# Audio-DAC.net
KiCad netlist of a schematic drawn in EAGLE
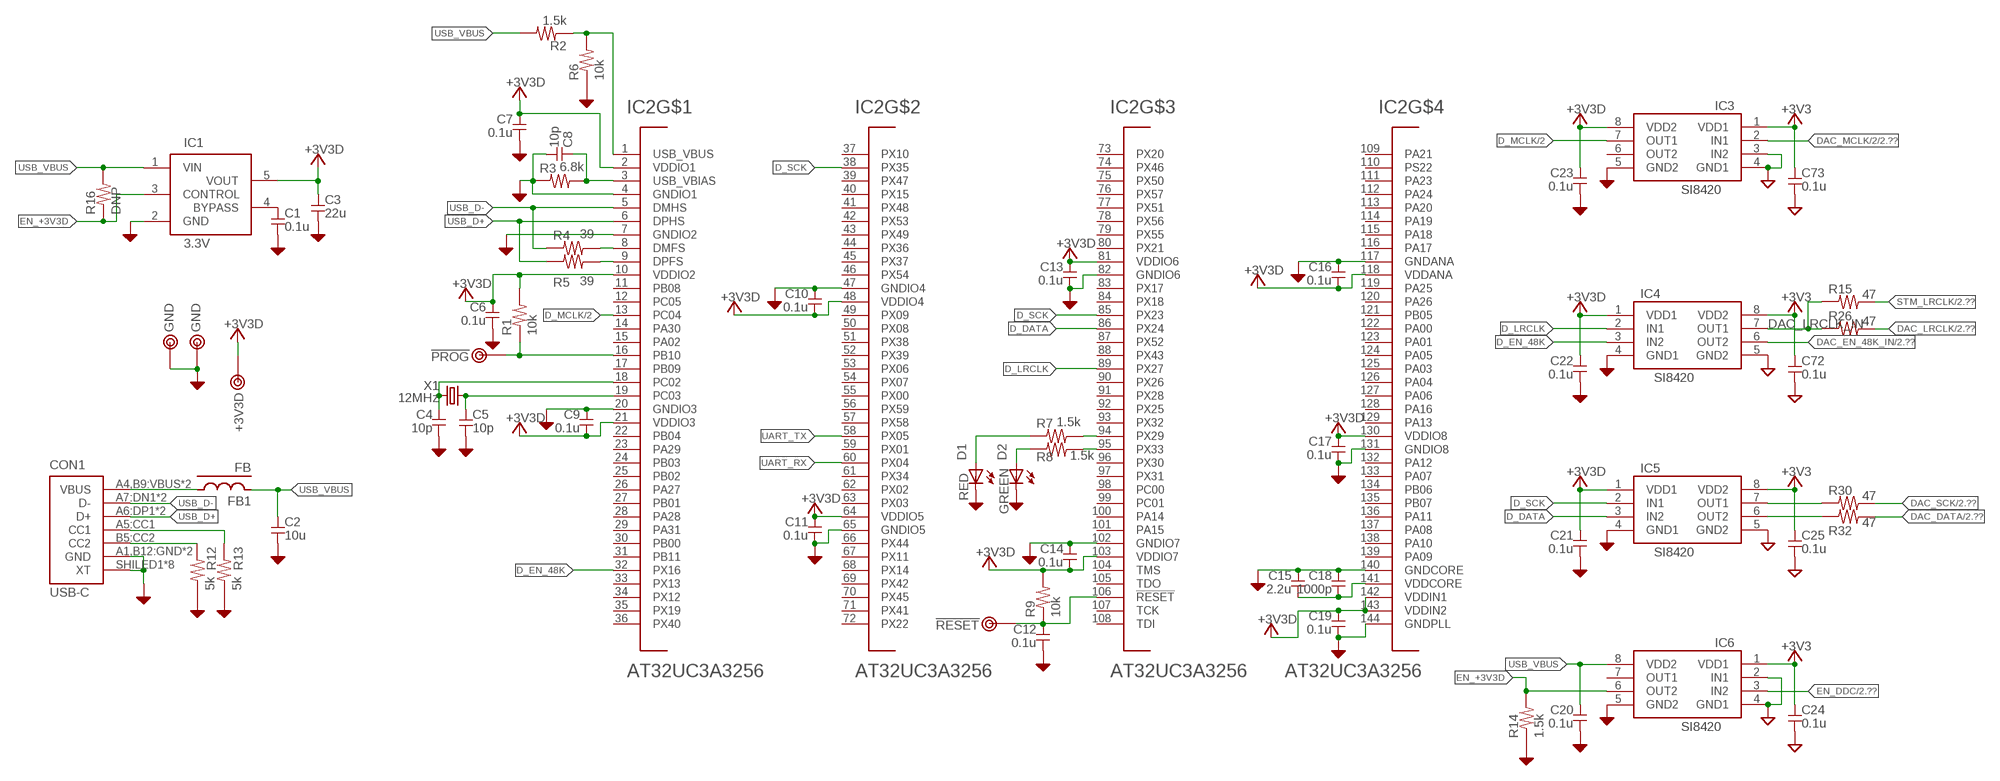
[diagram p0: schematic, sheet 1]
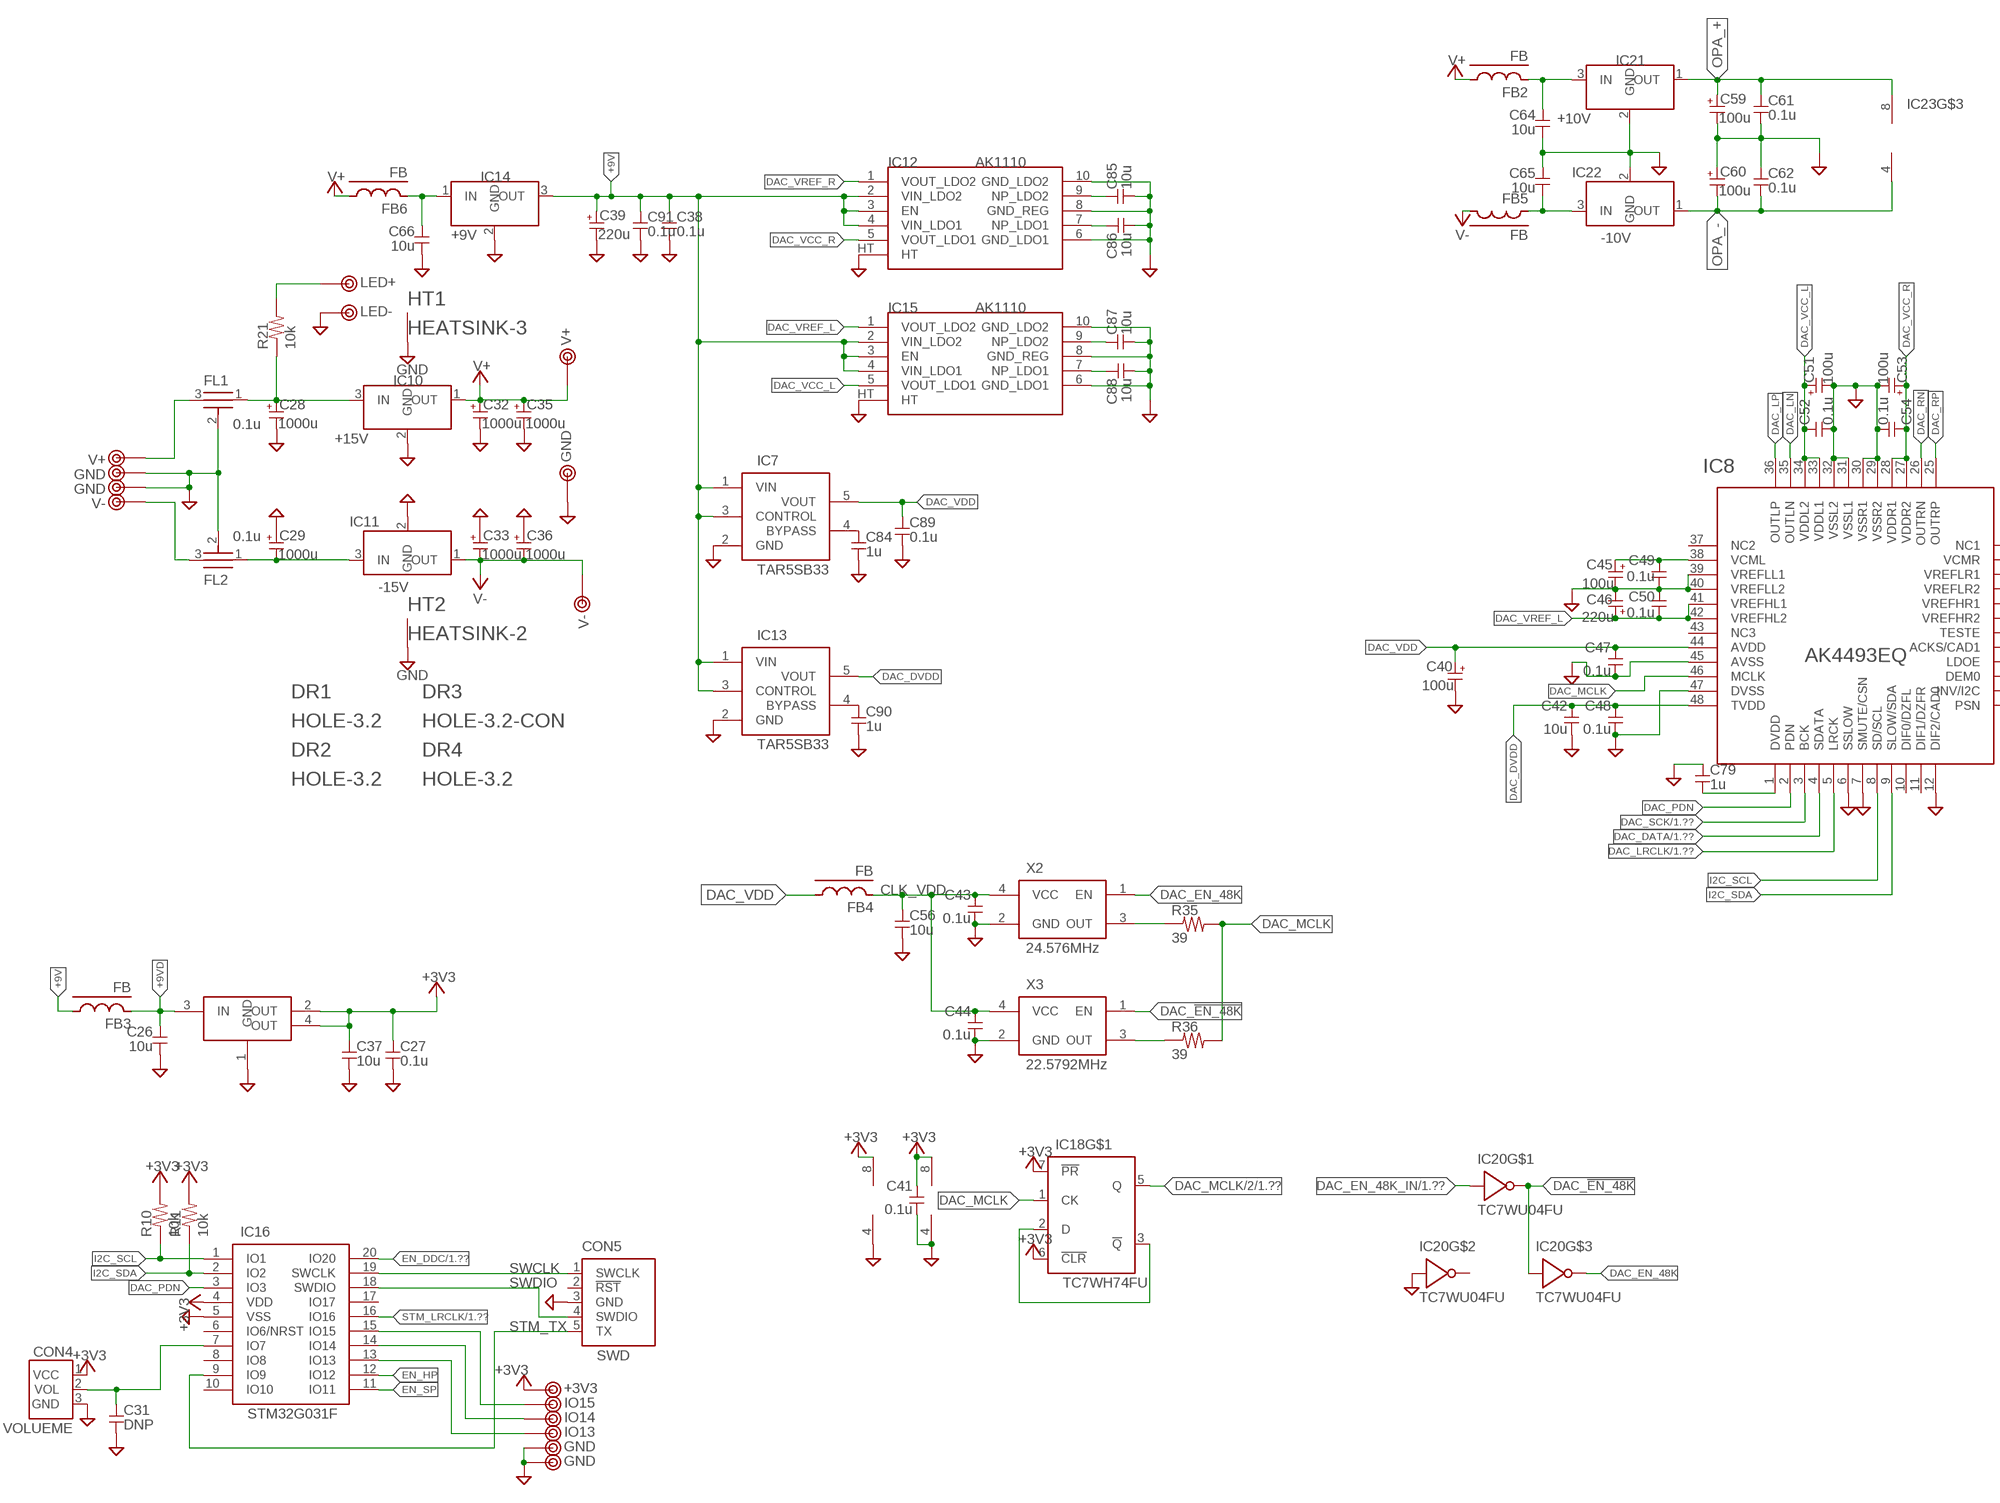
[diagram p1: schematic, sheet 2, part 1 of 2]
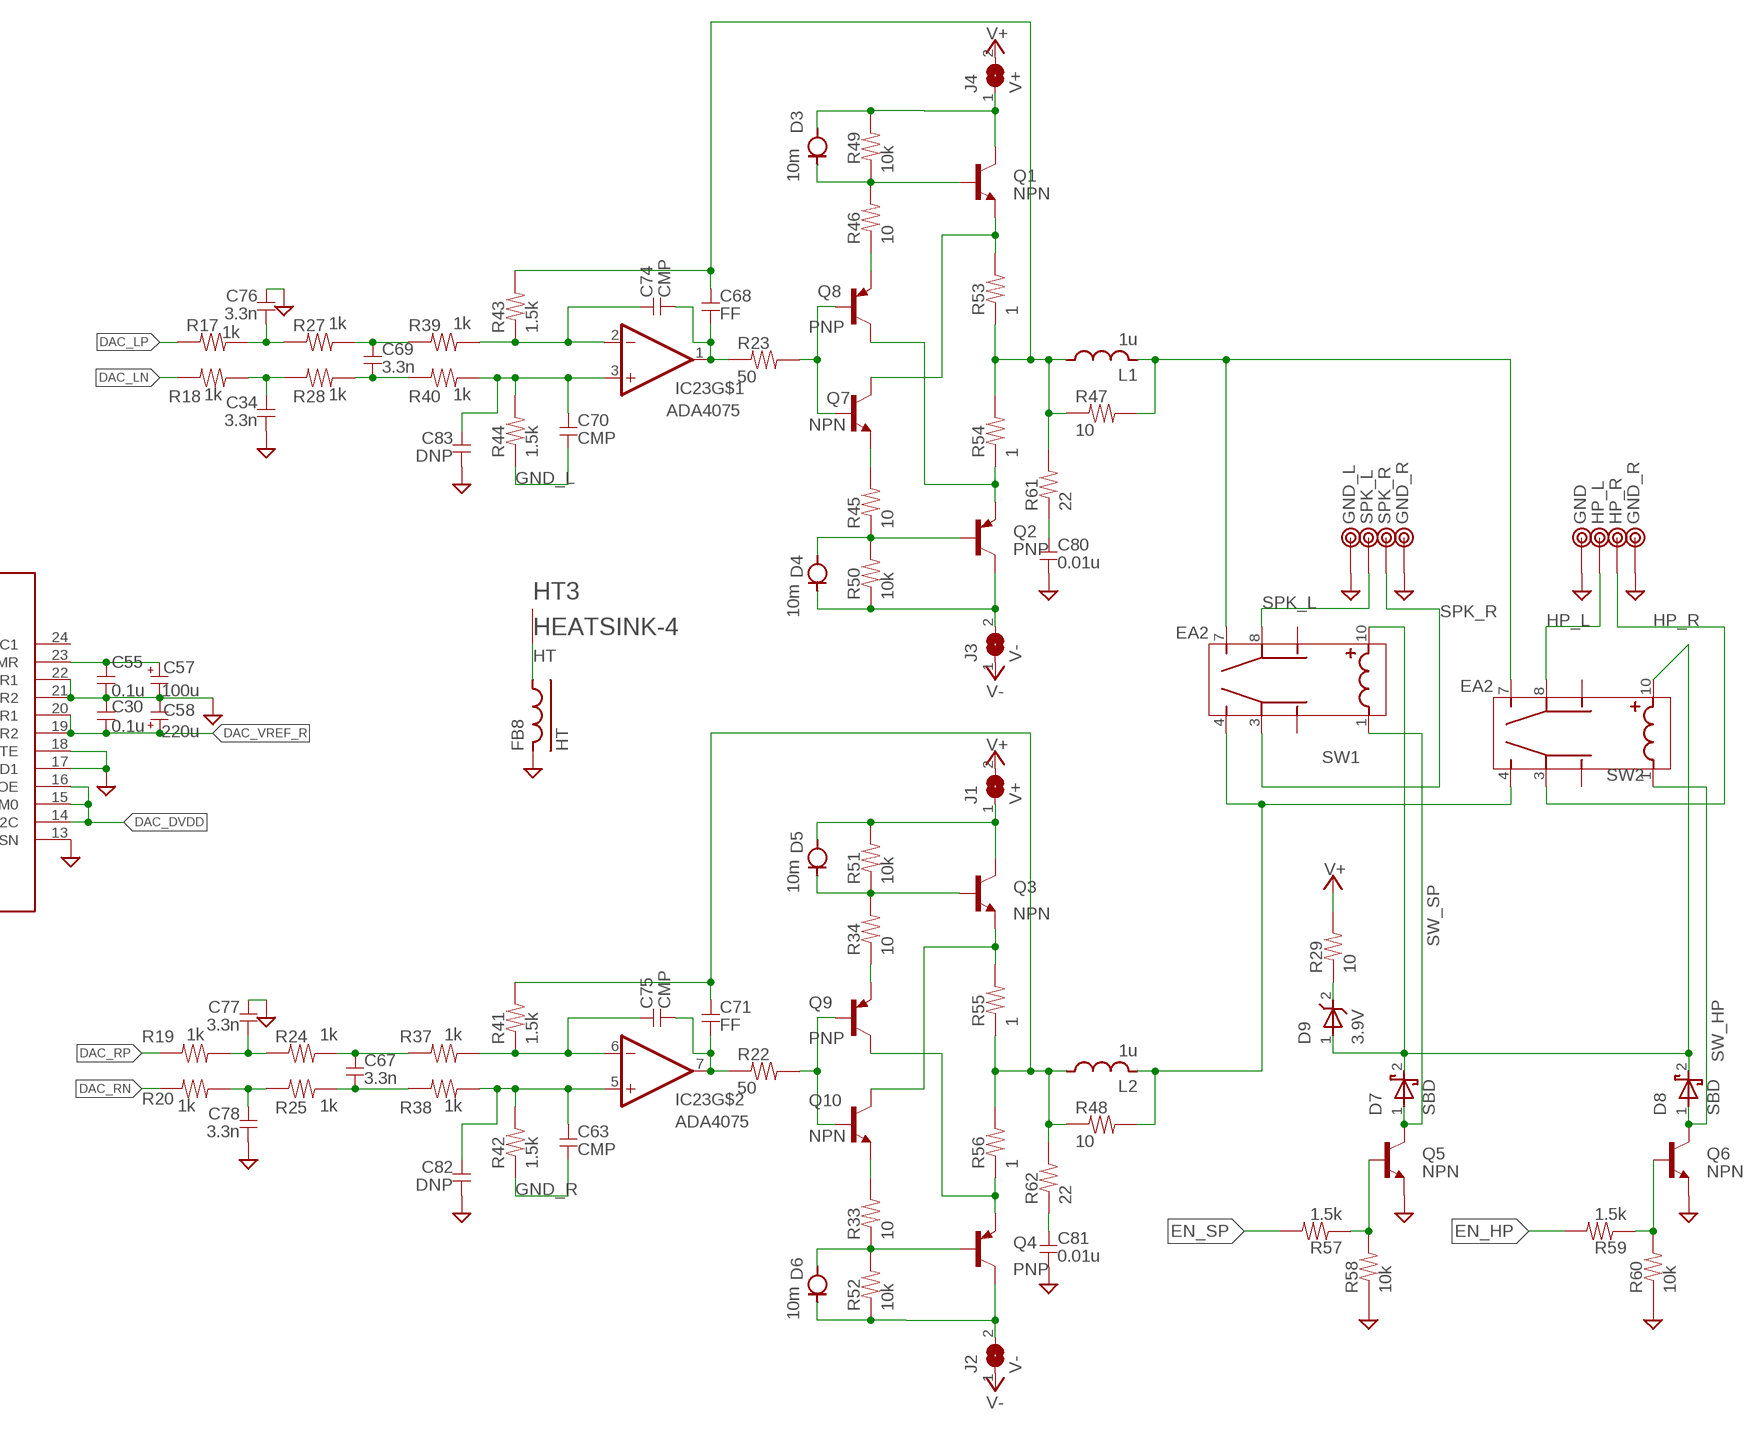
[diagram p2: schematic, sheet 2, part 2 of 2]

(export (version "E")
  (design (tool "Eeschema 10.0.6"))
  (components
    (comp (ref "C26")
      (value "10u")
      (footprint "eagle-import:2012")
      (libsource (lib "eagle-import") (part "C-2012"))
    )
    (comp (ref "C27")
      (value "0.1u")
      (footprint "eagle-import:1608C")
      (libsource (lib "eagle-import") (part "C-1608"))
    )
    (comp (ref "C28")
      (value "1000u")
      (footprint "eagle-import:E5-13")
      (libsource (lib "eagle-import") (part "CPOLE5-13"))
    )
    (comp (ref "C29")
      (value "1000u")
      (footprint "eagle-import:E5-13")
      (libsource (lib "eagle-import") (part "CPOLE5-13"))
    )
    (comp (ref "C30")
      (value "0.1u")
      (footprint "eagle-import:1608C")
      (libsource (lib "eagle-import") (part "C-1608"))
    )
    (comp (ref "C31")
      (value "DNP")
      (footprint "eagle-import:1608C")
      (libsource (lib "eagle-import") (part "C-1608"))
    )
    (comp (ref "C32")
      (value "1000u")
      (footprint "eagle-import:E5-10")
      (libsource (lib "eagle-import") (part "CPOLE5-10"))
    )
    (comp (ref "C33")
      (value "1000u")
      (footprint "eagle-import:E5-10")
      (libsource (lib "eagle-import") (part "CPOLE5-10"))
    )
    (comp (ref "C34")
      (value "3.3n")
      (footprint "eagle-import:1608C")
      (libsource (lib "eagle-import") (part "C-1608"))
    )
    (comp (ref "C35")
      (value "1000u")
      (footprint "eagle-import:E5-10")
      (libsource (lib "eagle-import") (part "CPOLE5-10"))
    )
    (comp (ref "C36")
      (value "1000u")
      (footprint "eagle-import:E5-10")
      (libsource (lib "eagle-import") (part "CPOLE5-10"))
    )
    (comp (ref "C37")
      (value "10u")
      (footprint "eagle-import:2012")
      (libsource (lib "eagle-import") (part "C-2012"))
    )
    (comp (ref "C38")
      (value "0.1u")
      (footprint "eagle-import:1608C")
      (libsource (lib "eagle-import") (part "C-1608"))
    )
    (comp (ref "C39")
      (value "220u")
      (footprint "eagle-import:E2,5-8")
      (libsource (lib "eagle-import") (part "CPOLE2.5-8"))
    )
    (comp (ref "C40")
      (value "100u")
      (footprint "eagle-import:E2.5-6.5")
      (libsource (lib "eagle-import") (part "CPOLE2.5-6.5"))
    )
    (comp (ref "C41")
      (value "0.1u")
      (footprint "eagle-import:1608C")
      (libsource (lib "eagle-import") (part "C-1608"))
    )
    (comp (ref "C42")
      (value "10u")
      (footprint "eagle-import:2012")
      (libsource (lib "eagle-import") (part "C-2012"))
    )
    (comp (ref "C43")
      (value "0.1u")
      (footprint "eagle-import:1608C")
      (libsource (lib "eagle-import") (part "C-1608"))
    )
    (comp (ref "C44")
      (value "0.1u")
      (footprint "eagle-import:1608C")
      (libsource (lib "eagle-import") (part "C-1608"))
    )
    (comp (ref "C45")
      (value "100u")
      (footprint "eagle-import:E2.5-6.5")
      (libsource (lib "eagle-import") (part "CPOLE2.5-6.5"))
    )
    (comp (ref "C46")
      (value "220u")
      (footprint "eagle-import:E2.5-6.5")
      (libsource (lib "eagle-import") (part "CPOLE2.5-6.5"))
    )
    (comp (ref "C47")
      (value "0.1u")
      (footprint "eagle-import:1608C")
      (libsource (lib "eagle-import") (part "C-1608"))
    )
    (comp (ref "C48")
      (value "0.1u")
      (footprint "eagle-import:1608C")
      (libsource (lib "eagle-import") (part "C-1608"))
    )
    (comp (ref "C49")
      (value "0.1u")
      (footprint "eagle-import:1608C")
      (libsource (lib "eagle-import") (part "C-1608"))
    )
    (comp (ref "C50")
      (value "0.1u")
      (footprint "eagle-import:1608C")
      (libsource (lib "eagle-import") (part "C-1608"))
    )
    (comp (ref "C51")
      (value "100u")
      (footprint "eagle-import:E2.5-6.5")
      (libsource (lib "eagle-import") (part "CPOLE2.5-6.5"))
    )
    (comp (ref "C52")
      (value "0.1u")
      (footprint "eagle-import:1608C")
      (libsource (lib "eagle-import") (part "C-1608"))
    )
    (comp (ref "C53")
      (value "100u")
      (footprint "eagle-import:E2.5-6.5")
      (libsource (lib "eagle-import") (part "CPOLE2.5-6.5"))
    )
    (comp (ref "C54")
      (value "0.1u")
      (footprint "eagle-import:1608C")
      (libsource (lib "eagle-import") (part "C-1608"))
    )
    (comp (ref "C55")
      (value "0.1u")
      (footprint "eagle-import:1608C")
      (libsource (lib "eagle-import") (part "C-1608"))
    )
    (comp (ref "C56")
      (value "10u")
      (footprint "eagle-import:2012")
      (libsource (lib "eagle-import") (part "C-2012"))
    )
    (comp (ref "C57")
      (value "100u")
      (footprint "eagle-import:E2.5-6.5")
      (libsource (lib "eagle-import") (part "CPOLE2.5-6.5"))
    )
    (comp (ref "C58")
      (value "220u")
      (footprint "eagle-import:E2.5-6.5")
      (libsource (lib "eagle-import") (part "CPOLE2.5-6.5"))
    )
    (comp (ref "C59")
      (value "100u")
      (footprint "eagle-import:E2,5-8")
      (libsource (lib "eagle-import") (part "CPOLE2.5-8"))
    )
    (comp (ref "C60")
      (value "100u")
      (footprint "eagle-import:E2,5-8")
      (libsource (lib "eagle-import") (part "CPOLE2.5-8"))
    )
    (comp (ref "C61")
      (value "0.1u")
      (footprint "eagle-import:1608C")
      (libsource (lib "eagle-import") (part "C-1608"))
    )
    (comp (ref "C62")
      (value "0.1u")
      (footprint "eagle-import:1608C")
      (libsource (lib "eagle-import") (part "C-1608"))
    )
    (comp (ref "C63")
      (value "CMP")
      (footprint "eagle-import:1608C")
      (libsource (lib "eagle-import") (part "C-1608"))
    )
    (comp (ref "C64")
      (value "10u")
      (footprint "eagle-import:2012")
      (libsource (lib "eagle-import") (part "C-2012"))
    )
    (comp (ref "C65")
      (value "10u")
      (footprint "eagle-import:2012")
      (libsource (lib "eagle-import") (part "C-2012"))
    )
    (comp (ref "C66")
      (value "10u")
      (footprint "eagle-import:2012")
      (libsource (lib "eagle-import") (part "C-2012"))
    )
    (comp (ref "C67")
      (value "3.3n")
      (footprint "eagle-import:1608C")
      (libsource (lib "eagle-import") (part "C-1608"))
    )
    (comp (ref "C68")
      (value "FF")
      (footprint "eagle-import:1608C")
      (libsource (lib "eagle-import") (part "C-1608"))
    )
    (comp (ref "C69")
      (value "3.3n")
      (footprint "eagle-import:1608C")
      (libsource (lib "eagle-import") (part "C-1608"))
    )
    (comp (ref "C70")
      (value "CMP")
      (footprint "eagle-import:1608C")
      (libsource (lib "eagle-import") (part "C-1608"))
    )
    (comp (ref "C71")
      (value "FF")
      (footprint "eagle-import:1608C")
      (libsource (lib "eagle-import") (part "C-1608"))
    )
    (comp (ref "C74")
      (value "CMP")
      (footprint "eagle-import:1608C")
      (libsource (lib "eagle-import") (part "C-1608"))
    )
    (comp (ref "C75")
      (value "CMP")
      (footprint "eagle-import:1608C")
      (libsource (lib "eagle-import") (part "C-1608"))
    )
    (comp (ref "C76")
      (value "3.3n")
      (footprint "eagle-import:1608C")
      (libsource (lib "eagle-import") (part "C-1608"))
    )
    (comp (ref "C77")
      (value "3.3n")
      (footprint "eagle-import:1608C")
      (libsource (lib "eagle-import") (part "C-1608"))
    )
    (comp (ref "C78")
      (value "3.3n")
      (footprint "eagle-import:1608C")
      (libsource (lib "eagle-import") (part "C-1608"))
    )
    (comp (ref "C79")
      (value "1u")
      (footprint "eagle-import:1608C")
      (libsource (lib "eagle-import") (part "C-1608"))
    )
    (comp (ref "C80")
      (value "0.01u")
      (footprint "eagle-import:2012")
      (libsource (lib "eagle-import") (part "C-2012"))
    )
    (comp (ref "C81")
      (value "0.01u")
      (footprint "eagle-import:2012")
      (libsource (lib "eagle-import") (part "C-2012"))
    )
    (comp (ref "C82")
      (value "DNP")
      (footprint "eagle-import:1608C")
      (libsource (lib "eagle-import") (part "C-1608"))
    )
    (comp (ref "C83")
      (value "DNP")
      (footprint "eagle-import:1608C")
      (libsource (lib "eagle-import") (part "C-1608"))
    )
    (comp (ref "C84")
      (value "1u")
      (footprint "eagle-import:1608C")
      (libsource (lib "eagle-import") (part "C-1608"))
    )
    (comp (ref "C85")
      (value "10u")
      (footprint "eagle-import:2012")
      (libsource (lib "eagle-import") (part "C-2012"))
    )
    (comp (ref "C86")
      (value "10u")
      (footprint "eagle-import:2012")
      (libsource (lib "eagle-import") (part "C-2012"))
    )
    (comp (ref "C87")
      (value "10u")
      (footprint "eagle-import:2012")
      (libsource (lib "eagle-import") (part "C-2012"))
    )
    (comp (ref "C88")
      (value "10u")
      (footprint "eagle-import:2012")
      (libsource (lib "eagle-import") (part "C-2012"))
    )
    (comp (ref "C89")
      (value "0.1u")
      (footprint "eagle-import:1608C")
      (libsource (lib "eagle-import") (part "C-1608"))
    )
    (comp (ref "C90")
      (value "1u")
      (footprint "eagle-import:1608C")
      (libsource (lib "eagle-import") (part "C-1608"))
    )
    (comp (ref "C91")
      (value "0.1u")
      (footprint "eagle-import:1608C")
      (libsource (lib "eagle-import") (part "C-1608"))
    )
    (comp (ref "CON4")
      (value "VOLUEME")
      (footprint "eagle-import:VOL_CON")
      (libsource (lib "eagle-import") (part "VOL_CON"))
    )
    (comp (ref "CON5")
      (value "SWD")
      (footprint "eagle-import:SWD_CON")
      (libsource (lib "eagle-import") (part "SWD_CON"))
    )
    (comp (ref "D3")
      (value "10m")
      (footprint "eagle-import:SOD123")
      (libsource (lib "eagle-import") (part "CRD-SMD"))
    )
    (comp (ref "D4")
      (value "10m")
      (footprint "eagle-import:SOD123")
      (libsource (lib "eagle-import") (part "CRD-SMD"))
    )
    (comp (ref "D5")
      (value "10m")
      (footprint "eagle-import:SOD123")
      (libsource (lib "eagle-import") (part "CRD-SMD"))
    )
    (comp (ref "D6")
      (value "10m")
      (footprint "eagle-import:SOD123")
      (libsource (lib "eagle-import") (part "CRD-SMD"))
    )
    (comp (ref "D7")
      (value "SBD")
      (footprint "eagle-import:SOD123")
      (libsource (lib "eagle-import") (part "SBD-1A2"))
    )
    (comp (ref "D8")
      (value "SBD")
      (footprint "eagle-import:SOD123")
      (libsource (lib "eagle-import") (part "SBD-1A2"))
    )
    (comp (ref "D9")
      (value "3.9V")
      (footprint "eagle-import:SOD123")
      (libsource (lib "eagle-import") (part "ZENER-SMD"))
    )
    (comp (ref "DR1")
      (value "HOLE-3.2")
      (footprint "eagle-import:HOLE_3.2")
      (libsource (lib "eagle-import") (part "HOLE-3.2"))
    )
    (comp (ref "DR2")
      (value "HOLE-3.2")
      (footprint "eagle-import:HOLE_3.2")
      (libsource (lib "eagle-import") (part "HOLE-3.2"))
    )
    (comp (ref "DR3")
      (value "HOLE-3.2-CON")
      (footprint "eagle-import:HOLE_3.2_CON")
      (libsource (lib "eagle-import") (part "HOLE-3.2-CON"))
    )
    (comp (ref "DR4")
      (value "HOLE-3.2")
      (footprint "eagle-import:HOLE_3.2")
      (libsource (lib "eagle-import") (part "HOLE-3.2"))
    )
    (comp (ref "FB2")
      (value "FB")
      (footprint "eagle-import:1608-J")
      (libsource (lib "eagle-import") (part "FB"))
    )
    (comp (ref "FB3")
      (value "FB")
      (footprint "eagle-import:1608-J")
      (libsource (lib "eagle-import") (part "FB"))
    )
    (comp (ref "FB4")
      (value "FB")
      (footprint "eagle-import:1608-J")
      (libsource (lib "eagle-import") (part "FB"))
    )
    (comp (ref "FB5")
      (value "FB")
      (footprint "eagle-import:1608-J")
      (libsource (lib "eagle-import") (part "FB"))
    )
    (comp (ref "FB6")
      (value "FB")
      (footprint "eagle-import:1608-J")
      (libsource (lib "eagle-import") (part "FB"))
    )
    (comp (ref "FB8")
      (value "HT")
      (footprint "eagle-import:2012-J")
      (libsource (lib "eagle-import") (part "FB-2012"))
    )
    (comp (ref "FL1")
      (value "0.1u")
      (footprint "eagle-import:FL1")
      (libsource (lib "eagle-import") (part "FL"))
    )
    (comp (ref "FL2")
      (value "0.1u")
      (footprint "eagle-import:FL1")
      (libsource (lib "eagle-import") (part "FL"))
    )
    (comp (ref "HT1")
      (value "HEATSINK-3")
      (footprint "eagle-import:HEATSINK3")
      (libsource (lib "eagle-import") (part "HEATSINK-3"))
    )
    (comp (ref "HT2")
      (value "HEATSINK-2")
      (footprint "eagle-import:HEATSINK2")
      (libsource (lib "eagle-import") (part "HEATSINK-2"))
    )
    (comp (ref "HT3")
      (value "HEATSINK-4")
      (footprint "eagle-import:HEATSINK4")
      (libsource (lib "eagle-import") (part "HEATSINK-4"))
    )
    (comp (ref "IC7")
      (value "TAR5SB33")
      (footprint "eagle-import:SOT23-5")
      (libsource (lib "eagle-import") (part "TAR5SB33"))
    )
    (comp (ref "IC8")
      (value "AK4493EQ")
      (footprint "eagle-import:LQFP48")
      (libsource (lib "eagle-import") (part "AK4493EQ"))
    )
    (comp (ref "IC9")
      (value "AZ1086H-3.3")
      (footprint "eagle-import:SOT223")
      (libsource (lib "eagle-import") (part "AZ1086?-H3.3"))
    )
    (comp (ref "IC10")
      (value "+15V")
      (footprint "eagle-import:REGULATOR_LED")
      (libsource (lib "eagle-import") (part "78X-LED"))
    )
    (comp (ref "IC11")
      (value "-15V")
      (footprint "eagle-import:REGULATOR_LED")
      (libsource (lib "eagle-import") (part "79X-LED"))
    )
    (comp (ref "IC12")
      (value "AK1110")
      (footprint "eagle-import:PLP10-SMD")
      (libsource (lib "eagle-import") (part "AK1110-SMD"))
    )
    (comp (ref "IC13")
      (value "TAR5SB33")
      (footprint "eagle-import:SOT23-5")
      (libsource (lib "eagle-import") (part "TAR5SB33"))
    )
    (comp (ref "IC14")
      (value "+9V")
      (footprint "eagle-import:TO-220")
      (libsource (lib "eagle-import") (part "78X-1"))
    )
    (comp (ref "IC15")
      (value "AK1110")
      (footprint "eagle-import:PLP10-SMD")
      (libsource (lib "eagle-import") (part "AK1110-SMD"))
    )
    (comp (ref "IC16")
      (value "STM32G031F")
      (footprint "eagle-import:TSSOP20")
      (libsource (lib "eagle-import") (part "STM32G031F"))
    )
    (comp (ref "IC18")
      (value "TC7WH74FU")
      (footprint "eagle-import:SSOP8-P-0.65")
      (libsource (lib "eagle-import") (part "TC7WH74FU"))
    )
    (comp (ref "IC20")
      (value "TC7WU04FU")
      (footprint "eagle-import:SSOP8-P-0.65")
      (libsource (lib "eagle-import") (part "TC7WU04FU"))
    )
    (comp (ref "IC21")
      (value "+10V")
      (footprint "eagle-import:REGULATOR_LED")
      (libsource (lib "eagle-import") (part "78X-LED"))
    )
    (comp (ref "IC22")
      (value "-10V")
      (footprint "eagle-import:REGULATOR_LED")
      (libsource (lib "eagle-import") (part "79X-LED"))
    )
    (comp (ref "IC23")
      (value "ADA4075")
      (footprint "eagle-import:SOP8")
      (libsource (lib "eagle-import") (part "OPA-2-SOP"))
    )
    (comp (ref "J1")
      (value "V+")
      (footprint "eagle-import:2012-J")
      (libsource (lib "eagle-import") (part "SJ-2012"))
    )
    (comp (ref "J2")
      (value "V-")
      (footprint "eagle-import:2012-J")
      (libsource (lib "eagle-import") (part "SJ-2012"))
    )
    (comp (ref "J3")
      (value "V-")
      (footprint "eagle-import:2012-J")
      (libsource (lib "eagle-import") (part "SJ-2012"))
    )
    (comp (ref "J4")
      (value "V+")
      (footprint "eagle-import:2012-J")
      (libsource (lib "eagle-import") (part "SJ-2012"))
    )
    (comp (ref "L1")
      (value "1u")
      (footprint "eagle-import:L7-10-2")
      (libsource (lib "eagle-import") (part "L-7-2"))
    )
    (comp (ref "L2")
      (value "1u")
      (footprint "eagle-import:L7-10-2")
      (libsource (lib "eagle-import") (part "L-7-2"))
    )
    (comp (ref "Q1")
      (value "NPN")
      (footprint "eagle-import:TO126")
      (libsource (lib "eagle-import") (part "NPN2SC3422"))
    )
    (comp (ref "Q2")
      (value "PNP")
      (footprint "eagle-import:TO126")
      (libsource (lib "eagle-import") (part "PNP2SA1359"))
    )
    (comp (ref "Q3")
      (value "NPN")
      (footprint "eagle-import:TO126")
      (libsource (lib "eagle-import") (part "NPN2SC3422"))
    )
    (comp (ref "Q4")
      (value "PNP")
      (footprint "eagle-import:TO126")
      (libsource (lib "eagle-import") (part "PNP2SA1359"))
    )
    (comp (ref "Q5")
      (value "NPN")
      (footprint "eagle-import:SC59")
      (libsource (lib "eagle-import") (part "NPN2SC3325"))
    )
    (comp (ref "Q6")
      (value "NPN")
      (footprint "eagle-import:SC59")
      (libsource (lib "eagle-import") (part "NPN2SC3325"))
    )
    (comp (ref "Q7")
      (value "NPN")
      (footprint "eagle-import:SC59")
      (libsource (lib "eagle-import") (part "NPN2SC3325"))
    )
    (comp (ref "Q8")
      (value "PNP")
      (footprint "eagle-import:SC59")
      (libsource (lib "eagle-import") (part "PNP2SA1313"))
    )
    (comp (ref "Q9")
      (value "PNP")
      (footprint "eagle-import:SC59")
      (libsource (lib "eagle-import") (part "PNP2SA1313"))
    )
    (comp (ref "Q10")
      (value "NPN")
      (footprint "eagle-import:SC59")
      (libsource (lib "eagle-import") (part "NPN2SC3325"))
    )
    (comp (ref "R10")
      (value "10k")
      (footprint "eagle-import:1608")
      (libsource (lib "eagle-import") (part "R-1608"))
    )
    (comp (ref "R11")
      (value "10k")
      (footprint "eagle-import:1608")
      (libsource (lib "eagle-import") (part "R-1608"))
    )
    (comp (ref "R17")
      (value "1k")
      (footprint "eagle-import:1608")
      (libsource (lib "eagle-import") (part "R-1608"))
    )
    (comp (ref "R18")
      (value "1k")
      (footprint "eagle-import:1608")
      (libsource (lib "eagle-import") (part "R-1608"))
    )
    (comp (ref "R19")
      (value "1k")
      (footprint "eagle-import:1608")
      (libsource (lib "eagle-import") (part "R-1608"))
    )
    (comp (ref "R20")
      (value "1k")
      (footprint "eagle-import:1608")
      (libsource (lib "eagle-import") (part "R-1608"))
    )
    (comp (ref "R21")
      (value "10k")
      (footprint "eagle-import:2012")
      (libsource (lib "eagle-import") (part "R-2012"))
    )
    (comp (ref "R22")
      (value "50")
      (footprint "eagle-import:1608")
      (libsource (lib "eagle-import") (part "R-1608"))
    )
    (comp (ref "R23")
      (value "50")
      (footprint "eagle-import:1608")
      (libsource (lib "eagle-import") (part "R-1608"))
    )
    (comp (ref "R24")
      (value "1k")
      (footprint "eagle-import:1608")
      (libsource (lib "eagle-import") (part "R-1608"))
    )
    (comp (ref "R25")
      (value "1k")
      (footprint "eagle-import:1608")
      (libsource (lib "eagle-import") (part "R-1608"))
    )
    (comp (ref "R27")
      (value "1k")
      (footprint "eagle-import:1608")
      (libsource (lib "eagle-import") (part "R-1608"))
    )
    (comp (ref "R28")
      (value "1k")
      (footprint "eagle-import:1608")
      (libsource (lib "eagle-import") (part "R-1608"))
    )
    (comp (ref "R29")
      (value "10")
      (footprint "eagle-import:2012")
      (libsource (lib "eagle-import") (part "R-2012"))
    )
    (comp (ref "R33")
      (value "10")
      (footprint "eagle-import:1608")
      (libsource (lib "eagle-import") (part "R-1608"))
    )
    (comp (ref "R34")
      (value "10")
      (footprint "eagle-import:1608")
      (libsource (lib "eagle-import") (part "R-1608"))
    )
    (comp (ref "R35")
      (value "39")
      (footprint "eagle-import:1608-J")
      (libsource (lib "eagle-import") (part "R-1608J"))
    )
    (comp (ref "R36")
      (value "39")
      (footprint "eagle-import:1608-J")
      (libsource (lib "eagle-import") (part "R-1608J"))
    )
    (comp (ref "R37")
      (value "1k")
      (footprint "eagle-import:1608")
      (libsource (lib "eagle-import") (part "R-1608"))
    )
    (comp (ref "R38")
      (value "1k")
      (footprint "eagle-import:1608")
      (libsource (lib "eagle-import") (part "R-1608"))
    )
    (comp (ref "R39")
      (value "1k")
      (footprint "eagle-import:1608")
      (libsource (lib "eagle-import") (part "R-1608"))
    )
    (comp (ref "R40")
      (value "1k")
      (footprint "eagle-import:1608")
      (libsource (lib "eagle-import") (part "R-1608"))
    )
    (comp (ref "R41")
      (value "1.5k")
      (footprint "eagle-import:1608")
      (libsource (lib "eagle-import") (part "R-1608"))
    )
    (comp (ref "R42")
      (value "1.5k")
      (footprint "eagle-import:1608")
      (libsource (lib "eagle-import") (part "R-1608"))
    )
    (comp (ref "R43")
      (value "1.5k")
      (footprint "eagle-import:1608")
      (libsource (lib "eagle-import") (part "R-1608"))
    )
    (comp (ref "R44")
      (value "1.5k")
      (footprint "eagle-import:1608")
      (libsource (lib "eagle-import") (part "R-1608"))
    )
    (comp (ref "R45")
      (value "10")
      (footprint "eagle-import:1608")
      (libsource (lib "eagle-import") (part "R-1608"))
    )
    (comp (ref "R46")
      (value "10")
      (footprint "eagle-import:1608")
      (libsource (lib "eagle-import") (part "R-1608"))
    )
    (comp (ref "R47")
      (value "10")
      (footprint "eagle-import:2012")
      (libsource (lib "eagle-import") (part "R-2012"))
    )
    (comp (ref "R48")
      (value "10")
      (footprint "eagle-import:2012")
      (libsource (lib "eagle-import") (part "R-2012"))
    )
    (comp (ref "R49")
      (value "10k")
      (footprint "eagle-import:1608")
      (libsource (lib "eagle-import") (part "R-1608"))
    )
    (comp (ref "R50")
      (value "10k")
      (footprint "eagle-import:1608")
      (libsource (lib "eagle-import") (part "R-1608"))
    )
    (comp (ref "R51")
      (value "10k")
      (footprint "eagle-import:1608")
      (libsource (lib "eagle-import") (part "R-1608"))
    )
    (comp (ref "R52")
      (value "10k")
      (footprint "eagle-import:1608")
      (libsource (lib "eagle-import") (part "R-1608"))
    )
    (comp (ref "R53")
      (value "1")
      (footprint "eagle-import:0207_2V")
      (libsource (lib "eagle-import") (part "R-2.5"))
    )
    (comp (ref "R54")
      (value "1")
      (footprint "eagle-import:0204_5")
      (libsource (lib "eagle-import") (part "R-5"))
    )
    (comp (ref "R55")
      (value "1")
      (footprint "eagle-import:0207_2V")
      (libsource (lib "eagle-import") (part "R-2.5"))
    )
    (comp (ref "R56")
      (value "1")
      (footprint "eagle-import:0207_2V")
      (libsource (lib "eagle-import") (part "R-2.5"))
    )
    (comp (ref "R57")
      (value "1.5k")
      (footprint "eagle-import:1608")
      (libsource (lib "eagle-import") (part "R-1608"))
    )
    (comp (ref "R58")
      (value "10k")
      (footprint "eagle-import:1608")
      (libsource (lib "eagle-import") (part "R-1608"))
    )
    (comp (ref "R59")
      (value "1.5k")
      (footprint "eagle-import:1608")
      (libsource (lib "eagle-import") (part "R-1608"))
    )
    (comp (ref "R60")
      (value "10k")
      (footprint "eagle-import:1608")
      (libsource (lib "eagle-import") (part "R-1608"))
    )
    (comp (ref "R61")
      (value "22")
      (footprint "eagle-import:2012")
      (libsource (lib "eagle-import") (part "R-2012"))
    )
    (comp (ref "R62")
      (value "22")
      (footprint "eagle-import:2012")
      (libsource (lib "eagle-import") (part "R-2012"))
    )
    (comp (ref "SW1")
      (value "EA2")
      (footprint "eagle-import:EA2")
      (libsource (lib "eagle-import") (part "EA2"))
    )
    (comp (ref "SW2")
      (value "EA2")
      (footprint "eagle-import:EA2")
      (libsource (lib "eagle-import") (part "EA2"))
    )
    (comp (ref "TP5")
      (value "V+")
      (footprint "eagle-import:TESTPIN-BIG")
      (libsource (lib "eagle-import") (part "TESTPIN-BIG"))
    )
    (comp (ref "TP6")
      (value "GND")
      (footprint "eagle-import:TESTPIN-BIG")
      (libsource (lib "eagle-import") (part "TESTPIN-BIG"))
    )
    (comp (ref "TP7")
      (value "GND")
      (footprint "eagle-import:TESTPIN-BIG")
      (libsource (lib "eagle-import") (part "TESTPIN-BIG"))
    )
    (comp (ref "TP8")
      (value "V-")
      (footprint "eagle-import:TESTPIN-BIG")
      (libsource (lib "eagle-import") (part "TESTPIN-BIG"))
    )
    (comp (ref "TP9")
      (value "IO15")
      (footprint "eagle-import:TESTPIN")
      (libsource (lib "eagle-import") (part "TESTPIN"))
    )
    (comp (ref "TP10")
      (value "IO14")
      (footprint "eagle-import:TESTPIN")
      (libsource (lib "eagle-import") (part "TESTPIN"))
    )
    (comp (ref "TP11")
      (value "V+")
      (footprint "eagle-import:TESTPIN-BIG")
      (libsource (lib "eagle-import") (part "TESTPIN-BIG"))
    )
    (comp (ref "TP12")
      (value "IO13")
      (footprint "eagle-import:TESTPIN")
      (libsource (lib "eagle-import") (part "TESTPIN"))
    )
    (comp (ref "TP13")
      (value "GND")
      (footprint "eagle-import:TESTPIN")
      (libsource (lib "eagle-import") (part "TESTPIN"))
    )
    (comp (ref "TP14")
      (value "GND")
      (footprint "eagle-import:TESTPIN")
      (libsource (lib "eagle-import") (part "TESTPIN"))
    )
    (comp (ref "TP15")
      (value "LED+")
      (footprint "eagle-import:TESTPIN")
      (libsource (lib "eagle-import") (part "TESTPIN"))
    )
    (comp (ref "TP16")
      (value "LED-")
      (footprint "eagle-import:TESTPIN")
      (libsource (lib "eagle-import") (part "TESTPIN"))
    )
    (comp (ref "TP17")
      (value "+3V3")
      (footprint "eagle-import:TESTPIN")
      (libsource (lib "eagle-import") (part "TESTPIN"))
    )
    (comp (ref "TP21")
      (value "V-")
      (footprint "eagle-import:TESTPIN-BIG")
      (libsource (lib "eagle-import") (part "TESTPIN-BIG"))
    )
    (comp (ref "TP22")
      (value "GND")
      (footprint "eagle-import:TESTPIN-BIG")
      (libsource (lib "eagle-import") (part "TESTPIN-BIG"))
    )
    (comp (ref "TP27")
      (value "GND_L")
      (footprint "eagle-import:TESTPIN-BIG")
      (libsource (lib "eagle-import") (part "TESTPIN-BIG"))
    )
    (comp (ref "TP28")
      (value "SPK_L")
      (footprint "eagle-import:TESTPIN-BIG")
      (libsource (lib "eagle-import") (part "TESTPIN-BIG"))
    )
    (comp (ref "TP29")
      (value "SPK_R")
      (footprint "eagle-import:TESTPIN-BIG")
      (libsource (lib "eagle-import") (part "TESTPIN-BIG"))
    )
    (comp (ref "TP30")
      (value "GND_R")
      (footprint "eagle-import:TESTPIN-BIG")
      (libsource (lib "eagle-import") (part "TESTPIN-BIG"))
    )
    (comp (ref "TP31")
      (value "GND")
      (footprint "eagle-import:TESTPIN-BIG")
      (libsource (lib "eagle-import") (part "TESTPIN-BIG"))
    )
    (comp (ref "TP32")
      (value "HP_L")
      (footprint "eagle-import:TESTPIN-BIG")
      (libsource (lib "eagle-import") (part "TESTPIN-BIG"))
    )
    (comp (ref "TP33")
      (value "HP_R")
      (footprint "eagle-import:TESTPIN-BIG")
      (libsource (lib "eagle-import") (part "TESTPIN-BIG"))
    )
    (comp (ref "TP34")
      (value "GND_R")
      (footprint "eagle-import:TESTPIN-BIG")
      (libsource (lib "eagle-import") (part "TESTPIN-BIG"))
    )
    (comp (ref "X2")
      (value "24.576MHz")
      (footprint "eagle-import:KC3225")
      (libsource (lib "eagle-import") (part "OSC-KC3225"))
    )
    (comp (ref "X3")
      (value "22.5792MHz")
      (footprint "eagle-import:KC3225")
      (libsource (lib "eagle-import") (part "OSC-KC3225"))
    )
    (comp (ref "C1")
      (value "0.1u")
      (footprint "eagle-import:1608C")
      (libsource (lib "eagle-import") (part "C-1608"))
    )
    (comp (ref "C2")
      (value "10u")
      (footprint "eagle-import:2012")
      (libsource (lib "eagle-import") (part "C-2012"))
    )
    (comp (ref "C3")
      (value "22u")
      (footprint "eagle-import:2012")
      (libsource (lib "eagle-import") (part "C-2012"))
    )
    (comp (ref "C4")
      (value "10p")
      (footprint "eagle-import:1608C")
      (libsource (lib "eagle-import") (part "C-1608"))
    )
    (comp (ref "C5")
      (value "10p")
      (footprint "eagle-import:1608C")
      (libsource (lib "eagle-import") (part "C-1608"))
    )
    (comp (ref "C6")
      (value "0.1u")
      (footprint "eagle-import:1608C")
      (libsource (lib "eagle-import") (part "C-1608"))
    )
    (comp (ref "C7")
      (value "0.1u")
      (footprint "eagle-import:1608C")
      (libsource (lib "eagle-import") (part "C-1608"))
    )
    (comp (ref "C8")
      (value "10p")
      (footprint "eagle-import:1608C")
      (libsource (lib "eagle-import") (part "C-1608"))
    )
    (comp (ref "C9")
      (value "0.1u")
      (footprint "eagle-import:1608C")
      (libsource (lib "eagle-import") (part "C-1608"))
    )
    (comp (ref "C10")
      (value "0.1u")
      (footprint "eagle-import:1608C")
      (libsource (lib "eagle-import") (part "C-1608"))
    )
    (comp (ref "C11")
      (value "0.1u")
      (footprint "eagle-import:1608C")
      (libsource (lib "eagle-import") (part "C-1608"))
    )
    (comp (ref "C12")
      (value "0.1u")
      (footprint "eagle-import:1608C")
      (libsource (lib "eagle-import") (part "C-1608"))
    )
    (comp (ref "C13")
      (value "0.1u")
      (footprint "eagle-import:1608C")
      (libsource (lib "eagle-import") (part "C-1608"))
    )
    (comp (ref "C14")
      (value "0.1u")
      (footprint "eagle-import:1608C")
      (libsource (lib "eagle-import") (part "C-1608"))
    )
    (comp (ref "C15")
      (value "2.2u")
      (footprint "eagle-import:2012")
      (libsource (lib "eagle-import") (part "C-2012"))
    )
    (comp (ref "C16")
      (value "0.1u")
      (footprint "eagle-import:1608C")
      (libsource (lib "eagle-import") (part "C-1608"))
    )
    (comp (ref "C17")
      (value "0.1u")
      (footprint "eagle-import:1608C")
      (libsource (lib "eagle-import") (part "C-1608"))
    )
    (comp (ref "C18")
      (value "1000p")
      (footprint "eagle-import:1608C")
      (libsource (lib "eagle-import") (part "C-1608"))
    )
    (comp (ref "C19")
      (value "0.1u")
      (footprint "eagle-import:1608C")
      (libsource (lib "eagle-import") (part "C-1608"))
    )
    (comp (ref "C20")
      (value "0.1u")
      (footprint "eagle-import:1608C")
      (libsource (lib "eagle-import") (part "C-1608"))
    )
    (comp (ref "C21")
      (value "0.1u")
      (footprint "eagle-import:1608C")
      (libsource (lib "eagle-import") (part "C-1608"))
    )
    (comp (ref "C22")
      (value "0.1u")
      (footprint "eagle-import:1608C")
      (libsource (lib "eagle-import") (part "C-1608"))
    )
    (comp (ref "C23")
      (value "0.1u")
      (footprint "eagle-import:1608C")
      (libsource (lib "eagle-import") (part "C-1608"))
    )
    (comp (ref "C24")
      (value "0.1u")
      (footprint "eagle-import:1608C")
      (libsource (lib "eagle-import") (part "C-1608"))
    )
    (comp (ref "C25")
      (value "0.1u")
      (footprint "eagle-import:1608C")
      (libsource (lib "eagle-import") (part "C-1608"))
    )
    (comp (ref "C72")
      (value "0.1u")
      (footprint "eagle-import:1608C")
      (libsource (lib "eagle-import") (part "C-1608"))
    )
    (comp (ref "C73")
      (value "0.1u")
      (footprint "eagle-import:1608C")
      (libsource (lib "eagle-import") (part "C-1608"))
    )
    (comp (ref "CON1")
      (value "USB-C")
      (footprint "eagle-import:5077CR-16-SMC2-BK-TR")
      (libsource (lib "eagle-import") (part "USB-C"))
    )
    (comp (ref "D1")
      (value "RED")
      (footprint "eagle-import:D1608")
      (libsource (lib "eagle-import") (part "LED-SMD1608"))
    )
    (comp (ref "D2")
      (value "GREEN")
      (footprint "eagle-import:D1608")
      (libsource (lib "eagle-import") (part "LED-SMD1608"))
    )
    (comp (ref "FB1")
      (value "FB")
      (footprint "eagle-import:1608-J")
      (libsource (lib "eagle-import") (part "FB"))
    )
    (comp (ref "IC1")
      (value "3.3V")
      (footprint "eagle-import:SOT23-5")
      (libsource (lib "eagle-import") (part "NJM12888"))
    )
    (comp (ref "IC2")
      (value "AT32UC3A3256")
      (footprint "eagle-import:TQFP144")
      (libsource (lib "eagle-import") (part "AT32UC3A3256"))
    )
    (comp (ref "IC3")
      (value "SI8420")
      (footprint "eagle-import:SOP8")
      (libsource (lib "eagle-import") (part "SI8420"))
    )
    (comp (ref "IC4")
      (value "SI8420")
      (footprint "eagle-import:SOP8")
      (libsource (lib "eagle-import") (part "SI8420"))
    )
    (comp (ref "IC5")
      (value "SI8420")
      (footprint "eagle-import:SOP8")
      (libsource (lib "eagle-import") (part "SI8420"))
    )
    (comp (ref "IC6")
      (value "SI8420")
      (footprint "eagle-import:SOP8")
      (libsource (lib "eagle-import") (part "SI8420"))
    )
    (comp (ref "R1")
      (value "10k")
      (footprint "eagle-import:1608")
      (libsource (lib "eagle-import") (part "R-1608"))
    )
    (comp (ref "R2")
      (value "1.5k")
      (footprint "eagle-import:1608")
      (libsource (lib "eagle-import") (part "R-1608"))
    )
    (comp (ref "R3")
      (value "6.8k")
      (footprint "eagle-import:1608")
      (libsource (lib "eagle-import") (part "R-1608"))
    )
    (comp (ref "R4")
      (value "39")
      (footprint "eagle-import:1608")
      (libsource (lib "eagle-import") (part "R-1608"))
    )
    (comp (ref "R5")
      (value "39")
      (footprint "eagle-import:1608")
      (libsource (lib "eagle-import") (part "R-1608"))
    )
    (comp (ref "R6")
      (value "10k")
      (footprint "eagle-import:1608")
      (libsource (lib "eagle-import") (part "R-1608"))
    )
    (comp (ref "R7")
      (value "1.5k")
      (footprint "eagle-import:1608")
      (libsource (lib "eagle-import") (part "R-1608"))
    )
    (comp (ref "R8")
      (value "1.5k")
      (footprint "eagle-import:1608")
      (libsource (lib "eagle-import") (part "R-1608"))
    )
    (comp (ref "R9")
      (value "10k")
      (footprint "eagle-import:1608")
      (libsource (lib "eagle-import") (part "R-1608"))
    )
    (comp (ref "R12")
      (value "5k")
      (footprint "eagle-import:1608")
      (libsource (lib "eagle-import") (part "R-1608"))
    )
    (comp (ref "R13")
      (value "5k")
      (footprint "eagle-import:1608")
      (libsource (lib "eagle-import") (part "R-1608"))
    )
    (comp (ref "R14")
      (value "1.5k")
      (footprint "eagle-import:1608")
      (libsource (lib "eagle-import") (part "R-1608"))
    )
    (comp (ref "R15")
      (value "47")
      (footprint "eagle-import:1608-J")
      (libsource (lib "eagle-import") (part "R-1608J"))
    )
    (comp (ref "R16")
      (value "DNP")
      (footprint "eagle-import:1608-J")
      (libsource (lib "eagle-import") (part "R-1608J"))
    )
    (comp (ref "R26")
      (value "47")
      (footprint "eagle-import:1608-J")
      (libsource (lib "eagle-import") (part "R-1608J"))
    )
    (comp (ref "R30")
      (value "47")
      (footprint "eagle-import:1608-J")
      (libsource (lib "eagle-import") (part "R-1608J"))
    )
    (comp (ref "R32")
      (value "47")
      (footprint "eagle-import:1608-J")
      (libsource (lib "eagle-import") (part "R-1608J"))
    )
    (comp (ref "TP1")
      (value "!PROG")
      (footprint "eagle-import:TESTPIN")
      (libsource (lib "eagle-import") (part "TESTPIN"))
    )
    (comp (ref "TP2")
      (value "!RESET")
      (footprint "eagle-import:TESTPIN")
      (libsource (lib "eagle-import") (part "TESTPIN"))
    )
    (comp (ref "TP3")
      (value "GND")
      (footprint "eagle-import:TESTPIN")
      (libsource (lib "eagle-import") (part "TESTPIN"))
    )
    (comp (ref "TP25")
      (value "GND")
      (footprint "eagle-import:TESTPIN")
      (libsource (lib "eagle-import") (part "TESTPIN"))
    )
    (comp (ref "TP26")
      (value "+3V3D")
      (footprint "eagle-import:TESTPIN")
      (libsource (lib "eagle-import") (part "TESTPIN"))
    )
    (comp (ref "X1")
      (value "12MHz")
      (footprint "eagle-import:HC49_S")
      (libsource (lib "eagle-import") (part "CRYSTALHC49S"))
    )
  )
  (nets
    (net (code "1") (name "+3V3") (class "Default")
      (node (ref "C24") (pin "1") (pinfunction "1_1") (pintype "passive"))
      (node (ref "C25") (pin "1") (pinfunction "1_1") (pintype "passive"))
      (node (ref "C27") (pin "1") (pinfunction "1_1") (pintype "passive"))
      (node (ref "C37") (pin "1") (pinfunction "1_1") (pintype "passive"))
      (node (ref "C41") (pin "1") (pinfunction "1_1") (pintype "passive"))
      (node (ref "C72") (pin "1") (pinfunction "1_1") (pintype "passive"))
      (node (ref "C73") (pin "1") (pinfunction "1_1") (pintype "passive"))
      (node (ref "CON4") (pin "1") (pinfunction "VCC_1") (pintype "power_in"))
      (node (ref "IC16") (pin "4") (pinfunction "VDD_4") (pintype "power_in"))
      (node (ref "IC18") (pin "6") (pinfunction "~{CLR}_6") (pintype "input"))
      (node (ref "IC18") (pin "7") (pinfunction "~{PR}_7") (pintype "input"))
      (node (ref "IC18") (pin "8") (pinfunction "V+_8") (pintype "power_in"))
      (node (ref "IC20") (pin "8") (pinfunction "V+_8") (pintype "power_in"))
      (node (ref "IC3") (pin "1") (pinfunction "VDD1_1") (pintype "power_in"))
      (node (ref "IC4") (pin "8") (pinfunction "VDD2_8") (pintype "power_in"))
      (node (ref "IC5") (pin "8") (pinfunction "VDD2_8") (pintype "power_in"))
      (node (ref "IC6") (pin "1") (pinfunction "VDD1_1") (pintype "power_in"))
      (node (ref "IC9") (pin "2") (pinfunction "OUT_2") (pintype "output"))
      (node (ref "IC9") (pin "4") (pinfunction "OUT_4") (pintype "output"))
      (node (ref "R10") (pin "2") (pinfunction "2_2") (pintype "passive"))
      (node (ref "R11") (pin "2") (pinfunction "2_2") (pintype "passive"))
      (node (ref "TP17") (pin "1") (pinfunction "1_1") (pintype "passive"))
    )
    (net (code "2") (name "+3V3D") (class "Default")
      (node (ref "C10") (pin "2") (pinfunction "2_2") (pintype "passive"))
      (node (ref "C11") (pin "1") (pinfunction "1_1") (pintype "passive"))
      (node (ref "C13") (pin "1") (pinfunction "1_1") (pintype "passive"))
      (node (ref "C14") (pin "2") (pinfunction "2_2") (pintype "passive"))
      (node (ref "C16") (pin "2") (pinfunction "2_2") (pintype "passive"))
      (node (ref "C17") (pin "1") (pinfunction "1_1") (pintype "passive"))
      (node (ref "C19") (pin "1") (pinfunction "1_1") (pintype "passive"))
      (node (ref "C21") (pin "1") (pinfunction "1_1") (pintype "passive"))
      (node (ref "C22") (pin "1") (pinfunction "1_1") (pintype "passive"))
      (node (ref "C23") (pin "1") (pinfunction "1_1") (pintype "passive"))
      (node (ref "C3") (pin "1") (pinfunction "1_1") (pintype "passive"))
      (node (ref "C6") (pin "1") (pinfunction "1_1") (pintype "passive"))
      (node (ref "C7") (pin "1") (pinfunction "1_1") (pintype "passive"))
      (node (ref "C9") (pin "2") (pinfunction "2_2") (pintype "passive"))
      (node (ref "IC1") (pin "5") (pinfunction "VOUT_5") (pintype "output"))
      (node (ref "IC2") (pin "10") (pinfunction "VDDIO2_10") (pintype "power_in"))
      (node (ref "IC2") (pin "103") (pinfunction "VDDIO7_103") (pintype "power_in"))
      (node (ref "IC2") (pin "118") (pinfunction "VDDANA_118") (pintype "power_in"))
      (node (ref "IC2") (pin "130") (pinfunction "VDDIO8_130") (pintype "power_in"))
      (node (ref "IC2") (pin "142") (pinfunction "VDDIN1_142") (pintype "power_in"))
      (node (ref "IC2") (pin "143") (pinfunction "VDDIN2_143") (pintype "power_in"))
      (node (ref "IC2") (pin "2") (pinfunction "VDDIO1_2") (pintype "power_in"))
      (node (ref "IC2") (pin "21") (pinfunction "VDDIO3_21") (pintype "power_in"))
      (node (ref "IC2") (pin "48") (pinfunction "VDDIO4_48") (pintype "power_in"))
      (node (ref "IC2") (pin "64") (pinfunction "VDDIO5_64") (pintype "power_in"))
      (node (ref "IC2") (pin "81") (pinfunction "VDDIO6_81") (pintype "power_in"))
      (node (ref "IC3") (pin "8") (pinfunction "VDD2_8") (pintype "power_in"))
      (node (ref "IC4") (pin "1") (pinfunction "VDD1_1") (pintype "power_in"))
      (node (ref "IC5") (pin "1") (pinfunction "VDD1_1") (pintype "power_in"))
      (node (ref "R1") (pin "2") (pinfunction "2_2") (pintype "passive"))
      (node (ref "R9") (pin "2") (pinfunction "2_2") (pintype "passive"))
      (node (ref "TP26") (pin "1") (pinfunction "1_1") (pintype "passive"))
    )
    (net (code "3") (name "+9V") (class "Default")
      (node (ref "C38") (pin "1") (pinfunction "1_1") (pintype "passive"))
      (node (ref "C39") (pin "+") (pinfunction "1_+") (pintype "passive"))
      (node (ref "C91") (pin "1") (pinfunction "1_1") (pintype "passive"))
      (node (ref "FB3") (pin "1") (pinfunction "1_1") (pintype "passive"))
      (node (ref "IC12") (pin "2") (pinfunction "VIN_LDO2_2") (pintype "input"))
      (node (ref "IC12") (pin "3") (pinfunction "EN_3") (pintype "input"))
      (node (ref "IC12") (pin "4") (pinfunction "VIN_LDO1_4") (pintype "input"))
      (node (ref "IC13") (pin "1") (pinfunction "VIN_1") (pintype "input"))
      (node (ref "IC13") (pin "3") (pinfunction "CONTROL_3") (pintype "input"))
      (node (ref "IC14") (pin "3") (pinfunction "OUT_3") (pintype "output"))
      (node (ref "IC15") (pin "2") (pinfunction "VIN_LDO2_2") (pintype "input"))
      (node (ref "IC15") (pin "3") (pinfunction "EN_3") (pintype "input"))
      (node (ref "IC15") (pin "4") (pinfunction "VIN_LDO1_4") (pintype "input"))
      (node (ref "IC7") (pin "1") (pinfunction "VIN_1") (pintype "input"))
      (node (ref "IC7") (pin "3") (pinfunction "CONTROL_3") (pintype "input"))
    )
    (net (code "4") (name "+9VD") (class "Default")
      (node (ref "C26") (pin "1") (pinfunction "1_1") (pintype "passive"))
      (node (ref "FB3") (pin "2") (pinfunction "2_2") (pintype "passive"))
      (node (ref "IC9") (pin "3") (pinfunction "IN_3") (pintype "input"))
    )
    (net (code "5") (name "CLK_VDD") (class "Default")
      (node (ref "C43") (pin "1") (pinfunction "1_1") (pintype "passive"))
      (node (ref "C44") (pin "1") (pinfunction "1_1") (pintype "passive"))
      (node (ref "C56") (pin "1") (pinfunction "1_1") (pintype "passive"))
      (node (ref "FB4") (pin "2") (pinfunction "2_2") (pintype "passive"))
      (node (ref "X2") (pin "4") (pinfunction "VCC_4") (pintype "input"))
      (node (ref "X3") (pin "4") (pinfunction "VCC_4") (pintype "input"))
    )
    (net (code "6") (name "DAC_DATA") (class "Default")
      (node (ref "IC8") (pin "4") (pinfunction "SDATA_4") (pintype "input"))
      (node (ref "R32") (pin "2") (pinfunction "2_2") (pintype "passive"))
    )
    (net (code "7") (name "DAC_DVDD") (class "Default")
      (node (ref "C42") (pin "1") (pinfunction "1_1") (pintype "passive"))
      (node (ref "C48") (pin "1") (pinfunction "1_1") (pintype "passive"))
      (node (ref "IC13") (pin "5") (pinfunction "VOUT_5") (pintype "output"))
      (node (ref "IC8") (pin "14") (pinfunction "INV/I2C_14") (pintype "input"))
      (node (ref "IC8") (pin "15") (pinfunction "DEM0_15") (pintype "input"))
      (node (ref "IC8") (pin "16") (pinfunction "LDOE_16") (pintype "bidirectional"))
      (node (ref "IC8") (pin "48") (pinfunction "TVDD_48") (pintype "power_in"))
    )
    (net (code "8") (name "DAC_EN_48K") (class "Default")
      (node (ref "IC20") (pin "5") (pinfunction "OUT_5") (pintype "output"))
      (node (ref "X2") (pin "1") (pinfunction "EN_1") (pintype "input"))
    )
    (net (code "9") (name "DAC_EN_48K_IN") (class "Default")
      (node (ref "IC20") (pin "1") (pinfunction "IN_1") (pintype "input"))
      (node (ref "IC4") (pin "6") (pinfunction "OUT2_6") (pintype "output"))
    )
    (net (code "10") (name "DAC_LN") (class "Default")
      (node (ref "IC8") (pin "35") (pinfunction "OUTLN_35") (pintype "output"))
      (node (ref "R18") (pin "1") (pinfunction "1_1") (pintype "passive"))
    )
    (net (code "11") (name "DAC_LP") (class "Default")
      (node (ref "IC8") (pin "36") (pinfunction "OUTLP_36") (pintype "output"))
      (node (ref "R17") (pin "1") (pinfunction "1_1") (pintype "passive"))
    )
    (net (code "12") (name "DAC_LRCLK") (class "Default")
      (node (ref "IC8") (pin "5") (pinfunction "LRCK_5") (pintype "input"))
      (node (ref "R26") (pin "2") (pinfunction "2_2") (pintype "passive"))
    )
    (net (code "13") (name "DAC_LRCLK_IN") (class "Default")
      (node (ref "IC4") (pin "7") (pinfunction "OUT1_7") (pintype "output"))
      (node (ref "R15") (pin "1") (pinfunction "1_1") (pintype "passive"))
      (node (ref "R26") (pin "1") (pinfunction "1_1") (pintype "passive"))
    )
    (net (code "14") (name "DAC_MCLK") (class "Default")
      (node (ref "IC18") (pin "1") (pinfunction "CK_1") (pintype "input"))
      (node (ref "IC8") (pin "46") (pinfunction "MCLK_46") (pintype "input"))
      (node (ref "R35") (pin "2") (pinfunction "2_2") (pintype "passive"))
      (node (ref "R36") (pin "2") (pinfunction "2_2") (pintype "passive"))
    )
    (net (code "15") (name "DAC_MCLK{slash}2") (class "Default")
      (node (ref "IC18") (pin "5") (pinfunction "Q_5") (pintype "output"))
      (node (ref "IC3") (pin "2") (pinfunction "IN1_2") (pintype "input"))
    )
    (net (code "16") (name "DAC_PDN") (class "Default")
      (node (ref "IC16") (pin "3") (pinfunction "IO3_3") (pintype "bidirectional"))
      (node (ref "IC8") (pin "2") (pinfunction "PDN_2") (pintype "input"))
    )
    (net (code "17") (name "DAC_RN") (class "Default")
      (node (ref "IC8") (pin "26") (pinfunction "OUTRN_26") (pintype "output"))
      (node (ref "R20") (pin "1") (pinfunction "1_1") (pintype "passive"))
    )
    (net (code "18") (name "DAC_RP") (class "Default")
      (node (ref "IC8") (pin "25") (pinfunction "OUTRP_25") (pintype "output"))
      (node (ref "R19") (pin "1") (pinfunction "1_1") (pintype "passive"))
    )
    (net (code "19") (name "DAC_SCK") (class "Default")
      (node (ref "IC8") (pin "3") (pinfunction "BCK_3") (pintype "input"))
      (node (ref "R30") (pin "2") (pinfunction "2_2") (pintype "passive"))
    )
    (net (code "20") (name "DAC_VCC_L") (class "Default")
      (node (ref "C51") (pin "+") (pinfunction "1_+") (pintype "passive"))
      (node (ref "C52") (pin "1") (pinfunction "1_1") (pintype "passive"))
      (node (ref "IC15") (pin "5") (pinfunction "VOUT_LDO1_5") (pintype "output"))
      (node (ref "IC8") (pin "33") (pinfunction "VDDL1_33") (pintype "power_in"))
      (node (ref "IC8") (pin "34") (pinfunction "VDDL2_34") (pintype "power_in"))
    )
    (net (code "21") (name "DAC_VCC_R") (class "Default")
      (node (ref "C53") (pin "+") (pinfunction "1_+") (pintype "passive"))
      (node (ref "C54") (pin "1") (pinfunction "1_1") (pintype "passive"))
      (node (ref "IC12") (pin "5") (pinfunction "VOUT_LDO1_5") (pintype "output"))
      (node (ref "IC8") (pin "27") (pinfunction "VDDR2_27") (pintype "power_in"))
      (node (ref "IC8") (pin "28") (pinfunction "VDDR1_28") (pintype "power_in"))
    )
    (net (code "22") (name "DAC_VDD") (class "Default")
      (node (ref "C40") (pin "+") (pinfunction "1_+") (pintype "passive"))
      (node (ref "C47") (pin "1") (pinfunction "1_1") (pintype "passive"))
      (node (ref "C89") (pin "1") (pinfunction "1_1") (pintype "passive"))
      (node (ref "FB4") (pin "1") (pinfunction "1_1") (pintype "passive"))
      (node (ref "IC7") (pin "5") (pinfunction "VOUT_5") (pintype "output"))
      (node (ref "IC8") (pin "44") (pinfunction "AVDD_44") (pintype "power_in"))
    )
    (net (code "23") (name "DAC_VREF_L") (class "Default")
      (node (ref "C46") (pin "+") (pinfunction "1_+") (pintype "passive"))
      (node (ref "C50") (pin "2") (pinfunction "2_2") (pintype "passive"))
      (node (ref "IC15") (pin "1") (pinfunction "VOUT_LDO2_1") (pintype "output"))
      (node (ref "IC8") (pin "41") (pinfunction "VREFHL1_41") (pintype "power_in"))
      (node (ref "IC8") (pin "42") (pinfunction "VREFHL2_42") (pintype "power_in"))
    )
    (net (code "24") (name "DAC_VREF_R") (class "Default")
      (node (ref "C30") (pin "2") (pinfunction "2_2") (pintype "passive"))
      (node (ref "C58") (pin "+") (pinfunction "1_+") (pintype "passive"))
      (node (ref "IC12") (pin "1") (pinfunction "VOUT_LDO2_1") (pintype "output"))
      (node (ref "IC8") (pin "19") (pinfunction "VREFHR2_19") (pintype "power_in"))
      (node (ref "IC8") (pin "20") (pinfunction "VREFHR1_20") (pintype "power_in"))
    )
    (net (code "25") (name "DAC_~{EN_48K}") (class "Default")
      (node (ref "IC20") (pin "3") (pinfunction "IN_3") (pintype "input"))
      (node (ref "IC20") (pin "7") (pinfunction "OUT_7") (pintype "output"))
      (node (ref "X3") (pin "1") (pinfunction "EN_1") (pintype "input"))
    )
    (net (code "26") (name "DGND") (class "Default")
      (node (ref "C1") (pin "2") (pinfunction "2_2") (pintype "passive"))
      (node (ref "C10") (pin "1") (pinfunction "1_1") (pintype "passive"))
      (node (ref "C11") (pin "2") (pinfunction "2_2") (pintype "passive"))
      (node (ref "C12") (pin "2") (pinfunction "2_2") (pintype "passive"))
      (node (ref "C13") (pin "2") (pinfunction "2_2") (pintype "passive"))
      (node (ref "C14") (pin "1") (pinfunction "1_1") (pintype "passive"))
      (node (ref "C15") (pin "1") (pinfunction "1_1") (pintype "passive"))
      (node (ref "C16") (pin "1") (pinfunction "1_1") (pintype "passive"))
      (node (ref "C17") (pin "2") (pinfunction "2_2") (pintype "passive"))
      (node (ref "C18") (pin "1") (pinfunction "1_1") (pintype "passive"))
      (node (ref "C19") (pin "2") (pinfunction "2_2") (pintype "passive"))
      (node (ref "C2") (pin "2") (pinfunction "2_2") (pintype "passive"))
      (node (ref "C20") (pin "2") (pinfunction "2_2") (pintype "passive"))
      (node (ref "C21") (pin "2") (pinfunction "2_2") (pintype "passive"))
      (node (ref "C22") (pin "2") (pinfunction "2_2") (pintype "passive"))
      (node (ref "C23") (pin "2") (pinfunction "2_2") (pintype "passive"))
      (node (ref "C3") (pin "2") (pinfunction "2_2") (pintype "passive"))
      (node (ref "C4") (pin "2") (pinfunction "2_2") (pintype "passive"))
      (node (ref "C5") (pin "2") (pinfunction "2_2") (pintype "passive"))
      (node (ref "C6") (pin "2") (pinfunction "2_2") (pintype "passive"))
      (node (ref "C7") (pin "2") (pinfunction "2_2") (pintype "passive"))
      (node (ref "C8") (pin "2") (pinfunction "2_2") (pintype "passive"))
      (node (ref "C9") (pin "1") (pinfunction "1_1") (pintype "passive"))
      (node (ref "CON1") (pin "A1,B12:GND") (pinfunction "GND_A1,B12:GND") (pintype "bidirectional"))
      (node (ref "CON1") (pin "B1,A12:GND") (pinfunction "GND_B1,A12:GND") (pintype "bidirectional"))
      (node (ref "CON1") (pin "SHILED1") (pinfunction "XT_SHILED1") (pintype "bidirectional"))
      (node (ref "CON1") (pin "SHILED2") (pinfunction "XT_SHILED2") (pintype "bidirectional"))
      (node (ref "CON1") (pin "SHILED3") (pinfunction "XT_SHILED3") (pintype "bidirectional"))
      (node (ref "CON1") (pin "SHILED4") (pinfunction "XT_SHILED4") (pintype "bidirectional"))
      (node (ref "CON1") (pin "SHILED5") (pinfunction "XT_SHILED5") (pintype "bidirectional"))
      (node (ref "CON1") (pin "SHILED6") (pinfunction "XT_SHILED6") (pintype "bidirectional"))
      (node (ref "CON1") (pin "SHILED7") (pinfunction "XT_SHILED7") (pintype "bidirectional"))
      (node (ref "CON1") (pin "SHILED8") (pinfunction "XT_SHILED8") (pintype "bidirectional"))
      (node (ref "D1") (pin "K") (pinfunction "K_K") (pintype "passive"))
      (node (ref "D2") (pin "K") (pinfunction "K_K") (pintype "passive"))
      (node (ref "IC1") (pin "2") (pinfunction "GND_2") (pintype "input"))
      (node (ref "IC2") (pin "102") (pinfunction "GNDIO7_102") (pintype "power_in"))
      (node (ref "IC2") (pin "117") (pinfunction "GNDANA_117") (pintype "power_in"))
      (node (ref "IC2") (pin "131") (pinfunction "GNDIO8_131") (pintype "power_in"))
      (node (ref "IC2") (pin "140") (pinfunction "GNDCORE_140") (pintype "power_in"))
      (node (ref "IC2") (pin "144") (pinfunction "GNDPLL_144") (pintype "power_in"))
      (node (ref "IC2") (pin "20") (pinfunction "GNDIO3_20") (pintype "power_in"))
      (node (ref "IC2") (pin "4") (pinfunction "GNDIO1_4") (pintype "power_in"))
      (node (ref "IC2") (pin "47") (pinfunction "GNDIO4_47") (pintype "power_in"))
      (node (ref "IC2") (pin "65") (pinfunction "GNDIO5_65") (pintype "power_in"))
      (node (ref "IC2") (pin "7") (pinfunction "GNDIO2_7") (pintype "power_in"))
      (node (ref "IC2") (pin "82") (pinfunction "GNDIO6_82") (pintype "power_in"))
      (node (ref "IC3") (pin "5") (pinfunction "GND2_5") (pintype "power_in"))
      (node (ref "IC4") (pin "4") (pinfunction "GND1_4") (pintype "power_in"))
      (node (ref "IC5") (pin "4") (pinfunction "GND1_4") (pintype "power_in"))
      (node (ref "IC6") (pin "5") (pinfunction "GND2_5") (pintype "power_in"))
      (node (ref "R12") (pin "1") (pinfunction "1_1") (pintype "passive"))
      (node (ref "R13") (pin "1") (pinfunction "1_1") (pintype "passive"))
      (node (ref "R14") (pin "1") (pinfunction "1_1") (pintype "passive"))
      (node (ref "R3") (pin "1") (pinfunction "1_1") (pintype "passive"))
      (node (ref "R6") (pin "1") (pinfunction "1_1") (pintype "passive"))
      (node (ref "TP25") (pin "1") (pinfunction "1_1") (pintype "passive"))
      (node (ref "TP3") (pin "1") (pinfunction "1_1") (pintype "passive"))
    )
    (net (code "27") (name "D_DATA") (class "Default")
      (node (ref "IC2") (pin "86") (pinfunction "PX24_86") (pintype "bidirectional"))
      (node (ref "IC5") (pin "3") (pinfunction "IN2_3") (pintype "input"))
    )
    (net (code "28") (name "D_EN_48K") (class "Default")
      (node (ref "IC2") (pin "32") (pinfunction "PX16_32") (pintype "bidirectional"))
      (node (ref "IC4") (pin "3") (pinfunction "IN2_3") (pintype "input"))
    )
    (net (code "29") (name "D_LRCLK") (class "Default")
      (node (ref "IC2") (pin "89") (pinfunction "PX27_89") (pintype "bidirectional"))
      (node (ref "IC4") (pin "2") (pinfunction "IN1_2") (pintype "input"))
    )
    (net (code "30") (name "D_MCLK{slash}2") (class "Default")
      (node (ref "IC2") (pin "13") (pinfunction "PC04_13") (pintype "bidirectional"))
      (node (ref "IC3") (pin "7") (pinfunction "OUT1_7") (pintype "output"))
    )
    (net (code "31") (name "D_SCK") (class "Default")
      (node (ref "IC2") (pin "38") (pinfunction "PX35_38") (pintype "bidirectional"))
      (node (ref "IC2") (pin "85") (pinfunction "PX23_85") (pintype "bidirectional"))
      (node (ref "IC5") (pin "2") (pinfunction "IN1_2") (pintype "input"))
    )
    (net (code "32") (name "EN_+3V3D") (class "Default")
      (node (ref "IC1") (pin "3") (pinfunction "CONTROL_3") (pintype "input"))
      (node (ref "IC6") (pin "6") (pinfunction "OUT2_6") (pintype "output"))
      (node (ref "R14") (pin "2") (pinfunction "2_2") (pintype "passive"))
      (node (ref "R16") (pin "1") (pinfunction "1_1") (pintype "passive"))
    )
    (net (code "33") (name "EN_DDC") (class "Default")
      (node (ref "IC16") (pin "20") (pinfunction "IO20_20") (pintype "bidirectional"))
      (node (ref "IC6") (pin "3") (pinfunction "IN2_3") (pintype "input"))
    )
    (net (code "34") (name "EN_HP") (class "Default")
      (node (ref "IC16") (pin "12") (pinfunction "IO12_12") (pintype "bidirectional"))
      (node (ref "R59") (pin "2") (pinfunction "2_2") (pintype "passive"))
    )
    (net (code "35") (name "EN_SP") (class "Default")
      (node (ref "IC16") (pin "11") (pinfunction "IO11_11") (pintype "bidirectional"))
      (node (ref "R57") (pin "2") (pinfunction "2_2") (pintype "passive"))
    )
    (net (code "36") (name "GND") (class "Default")
      (node (ref "C24") (pin "2") (pinfunction "2_2") (pintype "passive"))
      (node (ref "C25") (pin "2") (pinfunction "2_2") (pintype "passive"))
      (node (ref "C26") (pin "2") (pinfunction "2_2") (pintype "passive"))
      (node (ref "C27") (pin "2") (pinfunction "2_2") (pintype "passive"))
      (node (ref "C28") (pin "-") (pinfunction "2_-") (pintype "passive"))
      (node (ref "C29") (pin "+") (pinfunction "1_+") (pintype "passive"))
      (node (ref "C30") (pin "1") (pinfunction "1_1") (pintype "passive"))
      (node (ref "C31") (pin "2") (pinfunction "2_2") (pintype "passive"))
      (node (ref "C32") (pin "-") (pinfunction "2_-") (pintype "passive"))
      (node (ref "C33") (pin "+") (pinfunction "1_+") (pintype "passive"))
      (node (ref "C34") (pin "2") (pinfunction "2_2") (pintype "passive"))
      (node (ref "C35") (pin "-") (pinfunction "2_-") (pintype "passive"))
      (node (ref "C36") (pin "+") (pinfunction "1_+") (pintype "passive"))
      (node (ref "C37") (pin "2") (pinfunction "2_2") (pintype "passive"))
      (node (ref "C38") (pin "2") (pinfunction "2_2") (pintype "passive"))
      (node (ref "C39") (pin "-") (pinfunction "2_-") (pintype "passive"))
      (node (ref "C40") (pin "-") (pinfunction "2_-") (pintype "passive"))
      (node (ref "C41") (pin "2") (pinfunction "2_2") (pintype "passive"))
      (node (ref "C42") (pin "2") (pinfunction "2_2") (pintype "passive"))
      (node (ref "C43") (pin "2") (pinfunction "2_2") (pintype "passive"))
      (node (ref "C44") (pin "2") (pinfunction "2_2") (pintype "passive"))
      (node (ref "C45") (pin "-") (pinfunction "2_-") (pintype "passive"))
      (node (ref "C46") (pin "-") (pinfunction "2_-") (pintype "passive"))
      (node (ref "C47") (pin "2") (pinfunction "2_2") (pintype "passive"))
      (node (ref "C48") (pin "2") (pinfunction "2_2") (pintype "passive"))
      (node (ref "C49") (pin "2") (pinfunction "2_2") (pintype "passive"))
      (node (ref "C50") (pin "1") (pinfunction "1_1") (pintype "passive"))
      (node (ref "C51") (pin "-") (pinfunction "2_-") (pintype "passive"))
      (node (ref "C52") (pin "2") (pinfunction "2_2") (pintype "passive"))
      (node (ref "C53") (pin "-") (pinfunction "2_-") (pintype "passive"))
      (node (ref "C54") (pin "2") (pinfunction "2_2") (pintype "passive"))
      (node (ref "C55") (pin "2") (pinfunction "2_2") (pintype "passive"))
      (node (ref "C56") (pin "2") (pinfunction "2_2") (pintype "passive"))
      (node (ref "C57") (pin "-") (pinfunction "2_-") (pintype "passive"))
      (node (ref "C58") (pin "-") (pinfunction "2_-") (pintype "passive"))
      (node (ref "C59") (pin "-") (pinfunction "2_-") (pintype "passive"))
      (node (ref "C60") (pin "+") (pinfunction "1_+") (pintype "passive"))
      (node (ref "C61") (pin "2") (pinfunction "2_2") (pintype "passive"))
      (node (ref "C62") (pin "1") (pinfunction "1_1") (pintype "passive"))
      (node (ref "C64") (pin "2") (pinfunction "2_2") (pintype "passive"))
      (node (ref "C65") (pin "1") (pinfunction "1_1") (pintype "passive"))
      (node (ref "C66") (pin "2") (pinfunction "2_2") (pintype "passive"))
      (node (ref "C72") (pin "2") (pinfunction "2_2") (pintype "passive"))
      (node (ref "C73") (pin "2") (pinfunction "2_2") (pintype "passive"))
      (node (ref "C76") (pin "1") (pinfunction "1_1") (pintype "passive"))
      (node (ref "C77") (pin "1") (pinfunction "1_1") (pintype "passive"))
      (node (ref "C78") (pin "2") (pinfunction "2_2") (pintype "passive"))
      (node (ref "C79") (pin "1") (pinfunction "1_1") (pintype "passive"))
      (node (ref "C80") (pin "2") (pinfunction "2_2") (pintype "passive"))
      (node (ref "C81") (pin "2") (pinfunction "2_2") (pintype "passive"))
      (node (ref "C82") (pin "2") (pinfunction "2_2") (pintype "passive"))
      (node (ref "C83") (pin "2") (pinfunction "2_2") (pintype "passive"))
      (node (ref "C84") (pin "2") (pinfunction "2_2") (pintype "passive"))
      (node (ref "C85") (pin "2") (pinfunction "2_2") (pintype "passive"))
      (node (ref "C86") (pin "2") (pinfunction "2_2") (pintype "passive"))
      (node (ref "C87") (pin "2") (pinfunction "2_2") (pintype "passive"))
      (node (ref "C88") (pin "2") (pinfunction "2_2") (pintype "passive"))
      (node (ref "C89") (pin "2") (pinfunction "2_2") (pintype "passive"))
      (node (ref "C90") (pin "2") (pinfunction "2_2") (pintype "passive"))
      (node (ref "C91") (pin "2") (pinfunction "2_2") (pintype "passive"))
      (node (ref "CON4") (pin "3") (pinfunction "GND_3") (pintype "power_in"))
      (node (ref "CON5") (pin "3") (pinfunction "GND_3") (pintype "power_in"))
      (node (ref "FB8") (pin "2") (pinfunction "2_2") (pintype "passive"))
      (node (ref "FL1") (pin "2") (pinfunction "GND_2") (pintype "power_in"))
      (node (ref "FL2") (pin "2") (pinfunction "GND_2") (pintype "power_in"))
      (node (ref "HT1") (pin "HT1") (pinfunction "HT_HT1") (pintype "passive"))
      (node (ref "HT1") (pin "HT2") (pinfunction "HT_HT2") (pintype "passive"))
      (node (ref "HT2") (pin "HT1") (pinfunction "HT_HT1") (pintype "passive"))
      (node (ref "IC10") (pin "2") (pinfunction "GND_2") (pintype "input"))
      (node (ref "IC11") (pin "2") (pinfunction "GND_2") (pintype "input"))
      (node (ref "IC12") (pin "10") (pinfunction "GND_LDO2_10") (pintype "input"))
      (node (ref "IC12") (pin "6") (pinfunction "GND_LDO1_6") (pintype "input"))
      (node (ref "IC12") (pin "8") (pinfunction "GND_REG_8") (pintype "input"))
      (node (ref "IC12") (pin "HT") (pinfunction "HT_HT") (pintype "passive"))
      (node (ref "IC13") (pin "2") (pinfunction "GND_2") (pintype "input"))
      (node (ref "IC14") (pin "2") (pinfunction "GND_2") (pintype "input"))
      (node (ref "IC15") (pin "10") (pinfunction "GND_LDO2_10") (pintype "input"))
      (node (ref "IC15") (pin "6") (pinfunction "GND_LDO1_6") (pintype "input"))
      (node (ref "IC15") (pin "8") (pinfunction "GND_REG_8") (pintype "input"))
      (node (ref "IC15") (pin "HT") (pinfunction "HT_HT") (pintype "passive"))
      (node (ref "IC16") (pin "5") (pinfunction "VSS_5") (pintype "power_in"))
      (node (ref "IC18") (pin "4") (pinfunction "V-_4") (pintype "power_in"))
      (node (ref "IC20") (pin "4") (pinfunction "V-_4") (pintype "power_in"))
      (node (ref "IC20") (pin "6") (pinfunction "IN_6") (pintype "input"))
      (node (ref "IC21") (pin "2") (pinfunction "GND_2") (pintype "input"))
      (node (ref "IC22") (pin "2") (pinfunction "GND_2") (pintype "input"))
      (node (ref "IC3") (pin "3") (pinfunction "IN2_3") (pintype "input"))
      (node (ref "IC3") (pin "4") (pinfunction "GND1_4") (pintype "power_in"))
      (node (ref "IC4") (pin "5") (pinfunction "GND2_5") (pintype "power_in"))
      (node (ref "IC5") (pin "5") (pinfunction "GND2_5") (pintype "power_in"))
      (node (ref "IC6") (pin "2") (pinfunction "IN1_2") (pintype "input"))
      (node (ref "IC6") (pin "4") (pinfunction "GND1_4") (pintype "power_in"))
      (node (ref "IC7") (pin "2") (pinfunction "GND_2") (pintype "input"))
      (node (ref "IC8") (pin "12") (pinfunction "DIF2/CAD0_12") (pintype "input"))
      (node (ref "IC8") (pin "13") (pinfunction "PSN_13") (pintype "input"))
      (node (ref "IC8") (pin "17") (pinfunction "ACKS/CAD1_17") (pintype "input"))
      (node (ref "IC8") (pin "18") (pinfunction "TESTE_18") (pintype "input"))
      (node (ref "IC8") (pin "21") (pinfunction "VREFLR2_21") (pintype "power_in"))
      (node (ref "IC8") (pin "22") (pinfunction "VREFLR1_22") (pintype "power_in"))
      (node (ref "IC8") (pin "29") (pinfunction "VSSR2_29") (pintype "power_in"))
      (node (ref "IC8") (pin "30") (pinfunction "VSSR1_30") (pintype "power_in"))
      (node (ref "IC8") (pin "31") (pinfunction "VSSL1_31") (pintype "power_in"))
      (node (ref "IC8") (pin "32") (pinfunction "VSSL2_32") (pintype "power_in"))
      (node (ref "IC8") (pin "39") (pinfunction "VREFLL1_39") (pintype "power_in"))
      (node (ref "IC8") (pin "40") (pinfunction "VREFLL2_40") (pintype "power_in"))
      (node (ref "IC8") (pin "45") (pinfunction "AVSS_45") (pintype "power_in"))
      (node (ref "IC8") (pin "47") (pinfunction "DVSS_47") (pintype "power_in"))
      (node (ref "IC8") (pin "6") (pinfunction "SSLOW_6") (pintype "input"))
      (node (ref "IC8") (pin "7") (pinfunction "SMUTE/CSN_7") (pintype "input"))
      (node (ref "IC9") (pin "1") (pinfunction "GND_1") (pintype "input"))
      (node (ref "Q5") (pin "2") (pinfunction "E_2") (pintype "passive"))
      (node (ref "Q6") (pin "2") (pinfunction "E_2") (pintype "passive"))
      (node (ref "R58") (pin "1") (pinfunction "1_1") (pintype "passive"))
      (node (ref "R60") (pin "1") (pinfunction "1_1") (pintype "passive"))
      (node (ref "TP13") (pin "1") (pinfunction "1_1") (pintype "passive"))
      (node (ref "TP14") (pin "1") (pinfunction "1_1") (pintype "passive"))
      (node (ref "TP16") (pin "1") (pinfunction "1_1") (pintype "passive"))
      (node (ref "TP22") (pin "1") (pinfunction "1_1") (pintype "passive"))
      (node (ref "TP27") (pin "1") (pinfunction "1_1") (pintype "passive"))
      (node (ref "TP30") (pin "1") (pinfunction "1_1") (pintype "passive"))
      (node (ref "TP31") (pin "1") (pinfunction "1_1") (pintype "passive"))
      (node (ref "TP34") (pin "1") (pinfunction "1_1") (pintype "passive"))
      (node (ref "TP6") (pin "1") (pinfunction "1_1") (pintype "passive"))
      (node (ref "TP7") (pin "1") (pinfunction "1_1") (pintype "passive"))
      (node (ref "X2") (pin "2") (pinfunction "GND_2") (pintype "input"))
      (node (ref "X3") (pin "2") (pinfunction "GND_2") (pintype "input"))
    )
    (net (code "37") (name "GND_L") (class "Default")
      (node (ref "C70") (pin "2") (pinfunction "2_2") (pintype "passive"))
      (node (ref "R44") (pin "1") (pinfunction "1_1") (pintype "passive"))
    )
    (net (code "38") (name "GND_R") (class "Default")
      (node (ref "C63") (pin "2") (pinfunction "2_2") (pintype "passive"))
      (node (ref "R42") (pin "1") (pinfunction "1_1") (pintype "passive"))
    )
    (net (code "39") (name "HP_L") (class "Default")
      (node (ref "SW2") (pin "8") (pinfunction "COM2_8") (pintype "passive"))
      (node (ref "TP32") (pin "1") (pinfunction "1_1") (pintype "passive"))
    )
    (net (code "40") (name "HP_R") (class "Default")
      (node (ref "SW2") (pin "3") (pinfunction "COM1_3") (pintype "passive"))
      (node (ref "TP33") (pin "1") (pinfunction "1_1") (pintype "passive"))
    )
    (net (code "41") (name "HT") (class "Default")
      (node (ref "FB8") (pin "1") (pinfunction "1_1") (pintype "passive"))
      (node (ref "HT3") (pin "HT1") (pinfunction "HT_HT1") (pintype "passive"))
      (node (ref "HT3") (pin "HT2") (pinfunction "HT_HT2") (pintype "passive"))
    )
    (net (code "42") (name "I2C_SCL") (class "Default")
      (node (ref "IC16") (pin "1") (pinfunction "IO1_1") (pintype "bidirectional"))
      (node (ref "IC8") (pin "8") (pinfunction "SD/SCL_8") (pintype "bidirectional"))
      (node (ref "R10") (pin "1") (pinfunction "1_1") (pintype "passive"))
    )
    (net (code "43") (name "I2C_SDA") (class "Default")
      (node (ref "IC16") (pin "2") (pinfunction "IO2_2") (pintype "bidirectional"))
      (node (ref "IC8") (pin "9") (pinfunction "SLOW/SDA_9") (pintype "bidirectional"))
      (node (ref "R11") (pin "1") (pinfunction "1_1") (pintype "passive"))
    )
    (net (code "44") (name "Net-(C28-1)") (class "Default")
      (node (ref "C28") (pin "+") (pinfunction "1_+") (pintype "passive"))
      (node (ref "FL1") (pin "1") (pinfunction "OUT_1") (pintype "output"))
      (node (ref "IC10") (pin "3") (pinfunction "IN_3") (pintype "input"))
      (node (ref "R21") (pin "1") (pinfunction "1_1") (pintype "passive"))
    )
    (net (code "45") (name "Net-(C29-2)") (class "Default")
      (node (ref "C29") (pin "-") (pinfunction "2_-") (pintype "passive"))
      (node (ref "FL2") (pin "1") (pinfunction "OUT_1") (pintype "output"))
      (node (ref "IC11") (pin "3") (pinfunction "IN_3") (pintype "input"))
    )
    (net (code "46") (name "Net-(C34-Pad1)") (class "Default")
      (node (ref "C34") (pin "1") (pinfunction "1_1") (pintype "passive"))
      (node (ref "R18") (pin "2") (pinfunction "2_2") (pintype "passive"))
      (node (ref "R28") (pin "1") (pinfunction "1_1") (pintype "passive"))
    )
    (net (code "47") (name "Net-(C45-1)") (class "Default")
      (node (ref "C45") (pin "+") (pinfunction "1_+") (pintype "passive"))
      (node (ref "C49") (pin "1") (pinfunction "1_1") (pintype "passive"))
      (node (ref "IC8") (pin "38") (pinfunction "VCML_38") (pintype "power_in"))
    )
    (net (code "48") (name "Net-(C57-1)") (class "Default")
      (node (ref "C55") (pin "1") (pinfunction "1_1") (pintype "passive"))
      (node (ref "C57") (pin "+") (pinfunction "1_+") (pintype "passive"))
      (node (ref "IC8") (pin "23") (pinfunction "VCMR_23") (pintype "power_in"))
    )
    (net (code "49") (name "Net-(C67-Pad1)") (class "Default")
      (node (ref "C67") (pin "1") (pinfunction "1_1") (pintype "passive"))
      (node (ref "R24") (pin "2") (pinfunction "2_2") (pintype "passive"))
      (node (ref "R37") (pin "1") (pinfunction "1_1") (pintype "passive"))
    )
    (net (code "50") (name "Net-(C67-Pad2)") (class "Default")
      (node (ref "C67") (pin "2") (pinfunction "2_2") (pintype "passive"))
      (node (ref "R25") (pin "2") (pinfunction "2_2") (pintype "passive"))
      (node (ref "R38") (pin "1") (pinfunction "1_1") (pintype "passive"))
    )
    (net (code "51") (name "Net-(C68-Pad1)") (class "Default")
      (node (ref "C68") (pin "1") (pinfunction "1_1") (pintype "passive"))
      (node (ref "L1") (pin "1") (pinfunction "1_1") (pintype "passive"))
      (node (ref "R43") (pin "2") (pinfunction "2_2") (pintype "passive"))
      (node (ref "R47") (pin "1") (pinfunction "1_1") (pintype "passive"))
      (node (ref "R53") (pin "1") (pinfunction "1_1") (pintype "passive"))
      (node (ref "R54") (pin "2") (pinfunction "2_2") (pintype "passive"))
      (node (ref "R61") (pin "2") (pinfunction "2_2") (pintype "passive"))
    )
    (net (code "52") (name "Net-(C69-Pad1)") (class "Default")
      (node (ref "C69") (pin "1") (pinfunction "1_1") (pintype "passive"))
      (node (ref "R27") (pin "2") (pinfunction "2_2") (pintype "passive"))
      (node (ref "R39") (pin "1") (pinfunction "1_1") (pintype "passive"))
    )
    (net (code "53") (name "Net-(C69-Pad2)") (class "Default")
      (node (ref "C69") (pin "2") (pinfunction "2_2") (pintype "passive"))
      (node (ref "R28") (pin "2") (pinfunction "2_2") (pintype "passive"))
      (node (ref "R40") (pin "1") (pinfunction "1_1") (pintype "passive"))
    )
    (net (code "54") (name "Net-(C71-Pad1)") (class "Default")
      (node (ref "C71") (pin "1") (pinfunction "1_1") (pintype "passive"))
      (node (ref "L2") (pin "1") (pinfunction "1_1") (pintype "passive"))
      (node (ref "R41") (pin "2") (pinfunction "2_2") (pintype "passive"))
      (node (ref "R48") (pin "1") (pinfunction "1_1") (pintype "passive"))
      (node (ref "R55") (pin "1") (pinfunction "1_1") (pintype "passive"))
      (node (ref "R56") (pin "2") (pinfunction "2_2") (pintype "passive"))
      (node (ref "R62") (pin "2") (pinfunction "2_2") (pintype "passive"))
    )
    (net (code "55") (name "Net-(C76-Pad2)") (class "Default")
      (node (ref "C76") (pin "2") (pinfunction "2_2") (pintype "passive"))
      (node (ref "R17") (pin "2") (pinfunction "2_2") (pintype "passive"))
      (node (ref "R27") (pin "1") (pinfunction "1_1") (pintype "passive"))
    )
    (net (code "56") (name "Net-(C77-Pad2)") (class "Default")
      (node (ref "C77") (pin "2") (pinfunction "2_2") (pintype "passive"))
      (node (ref "R19") (pin "2") (pinfunction "2_2") (pintype "passive"))
      (node (ref "R24") (pin "1") (pinfunction "1_1") (pintype "passive"))
    )
    (net (code "57") (name "Net-(C78-Pad1)") (class "Default")
      (node (ref "C78") (pin "1") (pinfunction "1_1") (pintype "passive"))
      (node (ref "R20") (pin "2") (pinfunction "2_2") (pintype "passive"))
      (node (ref "R25") (pin "1") (pinfunction "1_1") (pintype "passive"))
    )
    (net (code "58") (name "Net-(C80-Pad1)") (class "Default")
      (node (ref "C80") (pin "1") (pinfunction "1_1") (pintype "passive"))
      (node (ref "R61") (pin "1") (pinfunction "1_1") (pintype "passive"))
    )
    (net (code "59") (name "Net-(C81-Pad1)") (class "Default")
      (node (ref "C81") (pin "1") (pinfunction "1_1") (pintype "passive"))
      (node (ref "R62") (pin "1") (pinfunction "1_1") (pintype "passive"))
    )
    (net (code "60") (name "Net-(CON1-CC1)") (class "Default")
      (node (ref "CON1") (pin "A5:CC1") (pinfunction "CC1_A5:CC1") (pintype "bidirectional"))
      (node (ref "R13") (pin "2") (pinfunction "2_2") (pintype "passive"))
    )
    (net (code "61") (name "Net-(CON1-CC2)") (class "Default")
      (node (ref "CON1") (pin "B5:CC2") (pinfunction "CC2_B5:CC2") (pintype "bidirectional"))
      (node (ref "R12") (pin "2") (pinfunction "2_2") (pintype "passive"))
    )
    (net (code "62") (name "Net-(CON1-VBUS-PadA4,B9:VBUS)") (class "Default")
      (node (ref "CON1") (pin "A4,B9:VBUS") (pinfunction "VBUS_A4,B9:VBUS") (pintype "output"))
      (node (ref "CON1") (pin "B4,A9:VBUS") (pinfunction "VBUS_B4,A9:VBUS") (pintype "output"))
      (node (ref "FB1") (pin "1") (pinfunction "1_1") (pintype "passive"))
    )
    (net (code "63") (name "Net-(CON4-VOL)") (class "Default")
      (node (ref "C31") (pin "1") (pinfunction "1_1") (pintype "passive"))
      (node (ref "CON4") (pin "2") (pinfunction "VOL_2") (pintype "bidirectional"))
      (node (ref "IC16") (pin "7") (pinfunction "IO7_7") (pintype "bidirectional"))
    )
    (net (code "64") (name "Net-(D1-PadA)") (class "Default")
      (node (ref "D1") (pin "A") (pinfunction "A_A") (pintype "passive"))
      (node (ref "R7") (pin "1") (pinfunction "1_1") (pintype "passive"))
    )
    (net (code "65") (name "Net-(D2-PadA)") (class "Default")
      (node (ref "D2") (pin "A") (pinfunction "A_A") (pintype "passive"))
      (node (ref "R8") (pin "1") (pinfunction "1_1") (pintype "passive"))
    )
    (net (code "66") (name "Net-(D3-A)") (class "Default")
      (node (ref "D3") (pin "1") (pinfunction "A_1") (pintype "passive"))
      (node (ref "J4") (pin "1") (pinfunction "1_1") (pintype "passive"))
      (node (ref "Q1") (pin "2") (pinfunction "C_2") (pintype "passive"))
      (node (ref "R49") (pin "2") (pinfunction "2_2") (pintype "passive"))
    )
    (net (code "67") (name "Net-(D3-K)") (class "Default")
      (node (ref "D3") (pin "2") (pinfunction "K_2") (pintype "passive"))
      (node (ref "Q1") (pin "3") (pinfunction "B_3") (pintype "passive"))
      (node (ref "R46") (pin "2") (pinfunction "2_2") (pintype "passive"))
      (node (ref "R49") (pin "1") (pinfunction "1_1") (pintype "passive"))
    )
    (net (code "68") (name "Net-(D4-A)") (class "Default")
      (node (ref "D4") (pin "1") (pinfunction "A_1") (pintype "passive"))
      (node (ref "Q2") (pin "3") (pinfunction "B_3") (pintype "passive"))
      (node (ref "R45") (pin "1") (pinfunction "1_1") (pintype "passive"))
      (node (ref "R50") (pin "2") (pinfunction "2_2") (pintype "passive"))
    )
    (net (code "69") (name "Net-(D4-K)") (class "Default")
      (node (ref "D4") (pin "2") (pinfunction "K_2") (pintype "passive"))
      (node (ref "J3") (pin "2") (pinfunction "2_2") (pintype "passive"))
      (node (ref "Q2") (pin "2") (pinfunction "C_2") (pintype "passive"))
      (node (ref "R50") (pin "1") (pinfunction "1_1") (pintype "passive"))
    )
    (net (code "70") (name "Net-(D5-A)") (class "Default")
      (node (ref "D5") (pin "1") (pinfunction "A_1") (pintype "passive"))
      (node (ref "J1") (pin "1") (pinfunction "1_1") (pintype "passive"))
      (node (ref "Q3") (pin "2") (pinfunction "C_2") (pintype "passive"))
      (node (ref "R51") (pin "2") (pinfunction "2_2") (pintype "passive"))
    )
    (net (code "71") (name "Net-(D5-K)") (class "Default")
      (node (ref "D5") (pin "2") (pinfunction "K_2") (pintype "passive"))
      (node (ref "Q3") (pin "3") (pinfunction "B_3") (pintype "passive"))
      (node (ref "R34") (pin "2") (pinfunction "2_2") (pintype "passive"))
      (node (ref "R51") (pin "1") (pinfunction "1_1") (pintype "passive"))
    )
    (net (code "72") (name "Net-(D6-A)") (class "Default")
      (node (ref "D6") (pin "1") (pinfunction "A_1") (pintype "passive"))
      (node (ref "Q4") (pin "3") (pinfunction "B_3") (pintype "passive"))
      (node (ref "R33") (pin "1") (pinfunction "1_1") (pintype "passive"))
      (node (ref "R52") (pin "2") (pinfunction "2_2") (pintype "passive"))
    )
    (net (code "73") (name "Net-(D6-K)") (class "Default")
      (node (ref "D6") (pin "2") (pinfunction "K_2") (pintype "passive"))
      (node (ref "J2") (pin "2") (pinfunction "2_2") (pintype "passive"))
      (node (ref "Q4") (pin "2") (pinfunction "C_2") (pintype "passive"))
      (node (ref "R52") (pin "1") (pinfunction "1_1") (pintype "passive"))
    )
    (net (code "74") (name "Net-(D7-K)") (class "Default")
      (node (ref "D7") (pin "2") (pinfunction "K_2") (pintype "bidirectional"))
      (node (ref "D8") (pin "2") (pinfunction "K_2") (pintype "bidirectional"))
      (node (ref "D9") (pin "1") (pinfunction "A_1") (pintype "bidirectional"))
      (node (ref "SW1") (pin "10") (pinfunction "L2_10") (pintype "passive"))
      (node (ref "SW2") (pin "10") (pinfunction "L2_10") (pintype "passive"))
    )
    (net (code "75") (name "Net-(D9-C)") (class "Default")
      (node (ref "D9") (pin "2") (pinfunction "C_2") (pintype "bidirectional"))
      (node (ref "R29") (pin "1") (pinfunction "1_1") (pintype "passive"))
    )
    (net (code "76") (name "Net-(FL1-IN)") (class "Default")
      (node (ref "FL1") (pin "3") (pinfunction "IN_3") (pintype "power_in"))
      (node (ref "TP5") (pin "1") (pinfunction "1_1") (pintype "passive"))
    )
    (net (code "77") (name "Net-(FL2-IN)") (class "Default")
      (node (ref "FL2") (pin "3") (pinfunction "IN_3") (pintype "power_in"))
      (node (ref "TP8") (pin "1") (pinfunction "1_1") (pintype "passive"))
    )
    (net (code "78") (name "Net-(IC1-BYPASS)") (class "Default")
      (node (ref "C1") (pin "1") (pinfunction "1_1") (pintype "passive"))
      (node (ref "IC1") (pin "4") (pinfunction "BYPASS_4") (pintype "passive"))
    )
    (net (code "79") (name "Net-(IC2A-DMFS)") (class "Default")
      (node (ref "IC2") (pin "8") (pinfunction "DMFS_8") (pintype "bidirectional"))
      (node (ref "R4") (pin "2") (pinfunction "2_2") (pintype "passive"))
    )
    (net (code "80") (name "Net-(IC2A-DPFS)") (class "Default")
      (node (ref "IC2") (pin "9") (pinfunction "DPFS_9") (pintype "bidirectional"))
      (node (ref "R5") (pin "2") (pinfunction "2_2") (pintype "passive"))
    )
    (net (code "81") (name "Net-(IC2A-PB10)") (class "Default")
      (node (ref "IC2") (pin "16") (pinfunction "PB10_16") (pintype "bidirectional"))
      (node (ref "R1") (pin "1") (pinfunction "1_1") (pintype "passive"))
      (node (ref "TP1") (pin "1") (pinfunction "1_1") (pintype "passive"))
    )
    (net (code "82") (name "Net-(IC2A-PC02)") (class "Default")
      (node (ref "C4") (pin "1") (pinfunction "1_1") (pintype "passive"))
      (node (ref "IC2") (pin "18") (pinfunction "PC02_18") (pintype "bidirectional"))
      (node (ref "X1") (pin "2") (pinfunction "2_2") (pintype "passive"))
    )
    (net (code "83") (name "Net-(IC2A-PC03)") (class "Default")
      (node (ref "C5") (pin "1") (pinfunction "1_1") (pintype "passive"))
      (node (ref "IC2") (pin "19") (pinfunction "PC03_19") (pintype "bidirectional"))
      (node (ref "X1") (pin "1") (pinfunction "1_1") (pintype "passive"))
    )
    (net (code "84") (name "Net-(IC2A-USB_VBIAS)") (class "Default")
      (node (ref "C8") (pin "1") (pinfunction "1_1") (pintype "passive"))
      (node (ref "IC2") (pin "3") (pinfunction "USB_VBIAS_3") (pintype "input"))
      (node (ref "R3") (pin "2") (pinfunction "2_2") (pintype "passive"))
    )
    (net (code "85") (name "Net-(IC2A-USB_VBUS)") (class "Default")
      (node (ref "IC2") (pin "1") (pinfunction "USB_VBUS_1") (pintype "input"))
      (node (ref "R2") (pin "1") (pinfunction "1_1") (pintype "passive"))
      (node (ref "R6") (pin "2") (pinfunction "2_2") (pintype "passive"))
    )
    (net (code "86") (name "Net-(IC2C-PX29)") (class "Default")
      (node (ref "IC2") (pin "94") (pinfunction "PX29_94") (pintype "bidirectional"))
      (node (ref "R7") (pin "2") (pinfunction "2_2") (pintype "passive"))
    )
    (net (code "87") (name "Net-(IC2C-PX33)") (class "Default")
      (node (ref "IC2") (pin "95") (pinfunction "PX33_95") (pintype "bidirectional"))
      (node (ref "R8") (pin "2") (pinfunction "2_2") (pintype "passive"))
    )
    (net (code "88") (name "Net-(IC2C-~{RESET})") (class "Default")
      (node (ref "C12") (pin "1") (pinfunction "1_1") (pintype "passive"))
      (node (ref "IC2") (pin "106") (pinfunction "~{RESET}_106") (pintype "input"))
      (node (ref "R9") (pin "1") (pinfunction "1_1") (pintype "passive"))
      (node (ref "TP2") (pin "1") (pinfunction "1_1") (pintype "passive"))
    )
    (net (code "89") (name "Net-(IC2D-VDDCORE)") (class "Default")
      (node (ref "C15") (pin "2") (pinfunction "2_2") (pintype "passive"))
      (node (ref "C18") (pin "2") (pinfunction "2_2") (pintype "passive"))
      (node (ref "IC2") (pin "141") (pinfunction "VDDCORE_141") (pintype "power_in"))
    )
    (net (code "90") (name "Net-(IC5-OUT1)") (class "Default")
      (node (ref "IC5") (pin "7") (pinfunction "OUT1_7") (pintype "output"))
      (node (ref "R30") (pin "1") (pinfunction "1_1") (pintype "passive"))
    )
    (net (code "91") (name "Net-(IC5-OUT2)") (class "Default")
      (node (ref "IC5") (pin "6") (pinfunction "OUT2_6") (pintype "output"))
      (node (ref "R32") (pin "1") (pinfunction "1_1") (pintype "passive"))
    )
    (net (code "92") (name "Net-(IC7-BYPASS)") (class "Default")
      (node (ref "C84") (pin "1") (pinfunction "1_1") (pintype "passive"))
      (node (ref "IC7") (pin "4") (pinfunction "BYPASS_4") (pintype "passive"))
    )
    (net (code "93") (name "Net-(IC8-DVDD)") (class "Default")
      (node (ref "C79") (pin "2") (pinfunction "2_2") (pintype "passive"))
      (node (ref "IC8") (pin "1") (pinfunction "DVDD_1") (pintype "power_in"))
    )
    (net (code "94") (name "Net-(IC12-NP_LDO1)") (class "Default")
      (node (ref "C86") (pin "1") (pinfunction "1_1") (pintype "passive"))
      (node (ref "IC12") (pin "7") (pinfunction "NP_LDO1_7") (pintype "passive"))
    )
    (net (code "95") (name "Net-(IC12-NP_LDO2)") (class "Default")
      (node (ref "C85") (pin "1") (pinfunction "1_1") (pintype "passive"))
      (node (ref "IC12") (pin "9") (pinfunction "NP_LDO2_9") (pintype "passive"))
    )
    (net (code "96") (name "Net-(IC13-BYPASS)") (class "Default")
      (node (ref "C90") (pin "1") (pinfunction "1_1") (pintype "passive"))
      (node (ref "IC13") (pin "4") (pinfunction "BYPASS_4") (pintype "passive"))
    )
    (net (code "97") (name "Net-(IC14-IN)") (class "Default")
      (node (ref "C66") (pin "1") (pinfunction "1_1") (pintype "passive"))
      (node (ref "FB6") (pin "2") (pinfunction "2_2") (pintype "passive"))
      (node (ref "IC14") (pin "1") (pinfunction "IN_1") (pintype "input"))
    )
    (net (code "98") (name "Net-(IC15-NP_LDO1)") (class "Default")
      (node (ref "C88") (pin "1") (pinfunction "1_1") (pintype "passive"))
      (node (ref "IC15") (pin "7") (pinfunction "NP_LDO1_7") (pintype "passive"))
    )
    (net (code "99") (name "Net-(IC15-NP_LDO2)") (class "Default")
      (node (ref "C87") (pin "1") (pinfunction "1_1") (pintype "passive"))
      (node (ref "IC15") (pin "9") (pinfunction "NP_LDO2_9") (pintype "passive"))
    )
    (net (code "100") (name "Net-(IC16-IO13)") (class "Default")
      (node (ref "IC16") (pin "13") (pinfunction "IO13_13") (pintype "bidirectional"))
      (node (ref "TP12") (pin "1") (pinfunction "1_1") (pintype "passive"))
    )
    (net (code "101") (name "Net-(IC16-IO14)") (class "Default")
      (node (ref "IC16") (pin "14") (pinfunction "IO14_14") (pintype "bidirectional"))
      (node (ref "TP10") (pin "1") (pinfunction "1_1") (pintype "passive"))
    )
    (net (code "102") (name "Net-(IC16-IO15)") (class "Default")
      (node (ref "IC16") (pin "15") (pinfunction "IO15_15") (pintype "bidirectional"))
      (node (ref "TP9") (pin "1") (pinfunction "1_1") (pintype "passive"))
    )
    (net (code "103") (name "Net-(IC18A-D)") (class "Default")
      (node (ref "IC18") (pin "2") (pinfunction "D_2") (pintype "input"))
      (node (ref "IC18") (pin "3") (pinfunction "~{Q}_3") (pintype "output"))
    )
    (net (code "104") (name "Net-(IC21-IN)") (class "Default")
      (node (ref "C64") (pin "1") (pinfunction "1_1") (pintype "passive"))
      (node (ref "FB2") (pin "2") (pinfunction "2_2") (pintype "passive"))
      (node (ref "IC21") (pin "3") (pinfunction "IN_3") (pintype "input"))
    )
    (net (code "105") (name "Net-(IC22-IN)") (class "Default")
      (node (ref "C65") (pin "2") (pinfunction "2_2") (pintype "passive"))
      (node (ref "FB5") (pin "2") (pinfunction "2_2") (pintype "passive"))
      (node (ref "IC22") (pin "3") (pinfunction "IN_3") (pintype "input"))
    )
    (net (code "106") (name "Net-(IC23A-+IN)") (class "Default")
      (node (ref "C70") (pin "1") (pinfunction "1_1") (pintype "passive"))
      (node (ref "C83") (pin "1") (pinfunction "1_1") (pintype "passive"))
      (node (ref "IC23") (pin "3") (pinfunction "+IN_3") (pintype "input"))
      (node (ref "R40") (pin "2") (pinfunction "2_2") (pintype "passive"))
      (node (ref "R44") (pin "2") (pinfunction "2_2") (pintype "passive"))
    )
    (net (code "107") (name "Net-(IC23A--IN)") (class "Default")
      (node (ref "C74") (pin "1") (pinfunction "1_1") (pintype "passive"))
      (node (ref "IC23") (pin "2") (pinfunction "-IN_2") (pintype "input"))
      (node (ref "R39") (pin "2") (pinfunction "2_2") (pintype "passive"))
      (node (ref "R43") (pin "1") (pinfunction "1_1") (pintype "passive"))
    )
    (net (code "108") (name "Net-(IC23A-OUT)") (class "Default")
      (node (ref "C68") (pin "2") (pinfunction "2_2") (pintype "passive"))
      (node (ref "C74") (pin "2") (pinfunction "2_2") (pintype "passive"))
      (node (ref "IC23") (pin "1") (pinfunction "OUT_1") (pintype "output"))
      (node (ref "R23") (pin "1") (pinfunction "1_1") (pintype "passive"))
    )
    (net (code "109") (name "Net-(IC23B-+IN)") (class "Default")
      (node (ref "C63") (pin "1") (pinfunction "1_1") (pintype "passive"))
      (node (ref "C82") (pin "1") (pinfunction "1_1") (pintype "passive"))
      (node (ref "IC23") (pin "5") (pinfunction "+IN_5") (pintype "input"))
      (node (ref "R38") (pin "2") (pinfunction "2_2") (pintype "passive"))
      (node (ref "R42") (pin "2") (pinfunction "2_2") (pintype "passive"))
    )
    (net (code "110") (name "Net-(IC23B--IN)") (class "Default")
      (node (ref "C75") (pin "1") (pinfunction "1_1") (pintype "passive"))
      (node (ref "IC23") (pin "6") (pinfunction "-IN_6") (pintype "input"))
      (node (ref "R37") (pin "2") (pinfunction "2_2") (pintype "passive"))
      (node (ref "R41") (pin "1") (pinfunction "1_1") (pintype "passive"))
    )
    (net (code "111") (name "Net-(IC23B-OUT)") (class "Default")
      (node (ref "C71") (pin "2") (pinfunction "2_2") (pintype "passive"))
      (node (ref "C75") (pin "2") (pinfunction "2_2") (pintype "passive"))
      (node (ref "IC23") (pin "7") (pinfunction "OUT_7") (pintype "output"))
      (node (ref "R22") (pin "1") (pinfunction "1_1") (pintype "passive"))
    )
    (net (code "112") (name "Net-(Q1-E)") (class "Default")
      (node (ref "Q1") (pin "1") (pinfunction "E_1") (pintype "passive"))
      (node (ref "Q7") (pin "3") (pinfunction "C_3") (pintype "passive"))
      (node (ref "R53") (pin "2") (pinfunction "2_2") (pintype "passive"))
    )
    (net (code "113") (name "Net-(Q2-E)") (class "Default")
      (node (ref "Q2") (pin "1") (pinfunction "E_1") (pintype "passive"))
      (node (ref "Q8") (pin "3") (pinfunction "C_3") (pintype "passive"))
      (node (ref "R54") (pin "1") (pinfunction "1_1") (pintype "passive"))
    )
    (net (code "114") (name "Net-(Q4-E)") (class "Default")
      (node (ref "Q4") (pin "1") (pinfunction "E_1") (pintype "passive"))
      (node (ref "Q9") (pin "3") (pinfunction "C_3") (pintype "passive"))
      (node (ref "R56") (pin "1") (pinfunction "1_1") (pintype "passive"))
    )
    (net (code "115") (name "Net-(Q5-B)") (class "Default")
      (node (ref "Q5") (pin "1") (pinfunction "B_1") (pintype "passive"))
      (node (ref "R57") (pin "1") (pinfunction "1_1") (pintype "passive"))
      (node (ref "R58") (pin "2") (pinfunction "2_2") (pintype "passive"))
    )
    (net (code "116") (name "Net-(Q6-B)") (class "Default")
      (node (ref "Q6") (pin "1") (pinfunction "B_1") (pintype "passive"))
      (node (ref "R59") (pin "1") (pinfunction "1_1") (pintype "passive"))
      (node (ref "R60") (pin "2") (pinfunction "2_2") (pintype "passive"))
    )
    (net (code "117") (name "Net-(Q7-B)") (class "Default")
      (node (ref "Q7") (pin "1") (pinfunction "B_1") (pintype "passive"))
      (node (ref "Q8") (pin "1") (pinfunction "B_1") (pintype "passive"))
      (node (ref "R23") (pin "2") (pinfunction "2_2") (pintype "passive"))
    )
    (net (code "118") (name "Net-(Q7-E)") (class "Default")
      (node (ref "Q7") (pin "2") (pinfunction "E_2") (pintype "passive"))
      (node (ref "R45") (pin "2") (pinfunction "2_2") (pintype "passive"))
    )
    (net (code "119") (name "Net-(Q8-E)") (class "Default")
      (node (ref "Q8") (pin "2") (pinfunction "E_2") (pintype "passive"))
      (node (ref "R46") (pin "1") (pinfunction "1_1") (pintype "passive"))
    )
    (net (code "120") (name "Net-(Q9-E)") (class "Default")
      (node (ref "Q9") (pin "2") (pinfunction "E_2") (pintype "passive"))
      (node (ref "R34") (pin "1") (pinfunction "1_1") (pintype "passive"))
    )
    (net (code "121") (name "Net-(Q10-B)") (class "Default")
      (node (ref "Q10") (pin "1") (pinfunction "B_1") (pintype "passive"))
      (node (ref "Q9") (pin "1") (pinfunction "B_1") (pintype "passive"))
      (node (ref "R22") (pin "2") (pinfunction "2_2") (pintype "passive"))
    )
    (net (code "122") (name "Net-(Q10-C)") (class "Default")
      (node (ref "Q10") (pin "3") (pinfunction "C_3") (pintype "passive"))
      (node (ref "Q3") (pin "1") (pinfunction "E_1") (pintype "passive"))
      (node (ref "R55") (pin "2") (pinfunction "2_2") (pintype "passive"))
    )
    (net (code "123") (name "Net-(Q10-E)") (class "Default")
      (node (ref "Q10") (pin "2") (pinfunction "E_2") (pintype "passive"))
      (node (ref "R33") (pin "2") (pinfunction "2_2") (pintype "passive"))
    )
    (net (code "124") (name "Net-(R21-Pad2)") (class "Default")
      (node (ref "R21") (pin "2") (pinfunction "2_2") (pintype "passive"))
      (node (ref "TP15") (pin "1") (pinfunction "1_1") (pintype "passive"))
    )
    (net (code "125") (name "Net-(SW1-A1)") (class "Default")
      (node (ref "L2") (pin "2") (pinfunction "2_2") (pintype "passive"))
      (node (ref "R48") (pin "2") (pinfunction "2_2") (pintype "passive"))
      (node (ref "SW1") (pin "4") (pinfunction "A1_4") (pintype "passive"))
      (node (ref "SW2") (pin "4") (pinfunction "A1_4") (pintype "passive"))
    )
    (net (code "126") (name "Net-(SW1-A2)") (class "Default")
      (node (ref "L1") (pin "2") (pinfunction "2_2") (pintype "passive"))
      (node (ref "R47") (pin "2") (pinfunction "2_2") (pintype "passive"))
      (node (ref "SW1") (pin "7") (pinfunction "A2_7") (pintype "passive"))
      (node (ref "SW2") (pin "7") (pinfunction "A2_7") (pintype "passive"))
    )
    (net (code "127") (name "Net-(X2-OUT)") (class "Default")
      (node (ref "R35") (pin "1") (pinfunction "1_1") (pintype "passive"))
      (node (ref "X2") (pin "3") (pinfunction "OUT_3") (pintype "output"))
    )
    (net (code "128") (name "Net-(X3-OUT)") (class "Default")
      (node (ref "R36") (pin "1") (pinfunction "1_1") (pintype "passive"))
      (node (ref "X3") (pin "3") (pinfunction "OUT_3") (pintype "output"))
    )
    (net (code "129") (name "OPA_+") (class "Default")
      (node (ref "C59") (pin "+") (pinfunction "1_+") (pintype "passive"))
      (node (ref "C61") (pin "1") (pinfunction "1_1") (pintype "passive"))
      (node (ref "IC21") (pin "1") (pinfunction "OUT_1") (pintype "output"))
      (node (ref "IC23") (pin "8") (pinfunction "V+_8") (pintype "power_in"))
    )
    (net (code "130") (name "OPA_-") (class "Default")
      (node (ref "C60") (pin "-") (pinfunction "2_-") (pintype "passive"))
      (node (ref "C62") (pin "2") (pinfunction "2_2") (pintype "passive"))
      (node (ref "IC22") (pin "1") (pinfunction "OUT_1") (pintype "output"))
      (node (ref "IC23") (pin "4") (pinfunction "V-_4") (pintype "power_in"))
    )
    (net (code "131") (name "SPK_L") (class "Default")
      (node (ref "SW1") (pin "8") (pinfunction "COM2_8") (pintype "passive"))
      (node (ref "TP28") (pin "1") (pinfunction "1_1") (pintype "passive"))
    )
    (net (code "132") (name "SPK_R") (class "Default")
      (node (ref "SW1") (pin "3") (pinfunction "COM1_3") (pintype "passive"))
      (node (ref "TP29") (pin "1") (pinfunction "1_1") (pintype "passive"))
    )
    (net (code "133") (name "STM_LRCLK") (class "Default")
      (node (ref "IC16") (pin "16") (pinfunction "IO16_16") (pintype "bidirectional"))
      (node (ref "R15") (pin "2") (pinfunction "2_2") (pintype "passive"))
    )
    (net (code "134") (name "STM_TX") (class "Default")
      (node (ref "CON5") (pin "5") (pinfunction "TX_5") (pintype "bidirectional"))
      (node (ref "IC16") (pin "9") (pinfunction "IO9_9") (pintype "bidirectional"))
    )
    (net (code "135") (name "SWCLK") (class "Default")
      (node (ref "CON5") (pin "1") (pinfunction "SWCLK_1") (pintype "bidirectional"))
      (node (ref "IC16") (pin "19") (pinfunction "SWCLK_19") (pintype "bidirectional"))
    )
    (net (code "136") (name "SWDIO") (class "Default")
      (node (ref "CON5") (pin "4") (pinfunction "SWDIO_4") (pintype "bidirectional"))
      (node (ref "IC16") (pin "18") (pinfunction "SWDIO_18") (pintype "bidirectional"))
    )
    (net (code "137") (name "SW_HP") (class "Default")
      (node (ref "D8") (pin "1") (pinfunction "A_1") (pintype "bidirectional"))
      (node (ref "Q6") (pin "3") (pinfunction "C_3") (pintype "passive"))
      (node (ref "SW2") (pin "1") (pinfunction "L1_1") (pintype "passive"))
    )
    (net (code "138") (name "SW_SP") (class "Default")
      (node (ref "D7") (pin "1") (pinfunction "A_1") (pintype "bidirectional"))
      (node (ref "Q5") (pin "3") (pinfunction "C_3") (pintype "passive"))
      (node (ref "SW1") (pin "1") (pinfunction "L1_1") (pintype "passive"))
    )
    (net (code "139") (name "UART_RX") (class "Default")
      (node (ref "IC2") (pin "60") (pinfunction "PX04_60") (pintype "bidirectional"))
    )
    (net (code "140") (name "UART_TX") (class "Default")
      (node (ref "IC2") (pin "58") (pinfunction "PX05_58") (pintype "bidirectional"))
    )
    (net (code "141") (name "USB_D+") (class "Default")
      (node (ref "CON1") (pin "A6:DP1") (pinfunction "D+_A6:DP1") (pintype "bidirectional"))
      (node (ref "CON1") (pin "B6:DP2") (pinfunction "D+_B6:DP2") (pintype "bidirectional"))
      (node (ref "IC2") (pin "6") (pinfunction "DPHS_6") (pintype "bidirectional"))
      (node (ref "R5") (pin "1") (pinfunction "1_1") (pintype "passive"))
    )
    (net (code "142") (name "USB_D-") (class "Default")
      (node (ref "CON1") (pin "A7:DN1") (pinfunction "D-_A7:DN1") (pintype "bidirectional"))
      (node (ref "CON1") (pin "B7:DN2") (pinfunction "D-_B7:DN2") (pintype "bidirectional"))
      (node (ref "IC2") (pin "5") (pinfunction "DMHS_5") (pintype "bidirectional"))
      (node (ref "R4") (pin "1") (pinfunction "1_1") (pintype "passive"))
    )
    (net (code "143") (name "USB_VBUS") (class "Default")
      (node (ref "C2") (pin "1") (pinfunction "1_1") (pintype "passive"))
      (node (ref "C20") (pin "1") (pinfunction "1_1") (pintype "passive"))
      (node (ref "FB1") (pin "2") (pinfunction "2_2") (pintype "passive"))
      (node (ref "IC1") (pin "1") (pinfunction "VIN_1") (pintype "input"))
      (node (ref "IC6") (pin "8") (pinfunction "VDD2_8") (pintype "power_in"))
      (node (ref "R16") (pin "2") (pinfunction "2_2") (pintype "passive"))
      (node (ref "R2") (pin "2") (pinfunction "2_2") (pintype "passive"))
    )
    (net (code "144") (name "V+") (class "Default")
      (node (ref "C32") (pin "+") (pinfunction "1_+") (pintype "passive"))
      (node (ref "C35") (pin "+") (pinfunction "1_+") (pintype "passive"))
      (node (ref "FB2") (pin "1") (pinfunction "1_1") (pintype "passive"))
      (node (ref "FB6") (pin "1") (pinfunction "1_1") (pintype "passive"))
      (node (ref "IC10") (pin "1") (pinfunction "OUT_1") (pintype "output"))
      (node (ref "J1") (pin "2") (pinfunction "2_2") (pintype "passive"))
      (node (ref "J4") (pin "2") (pinfunction "2_2") (pintype "passive"))
      (node (ref "R29") (pin "2") (pinfunction "2_2") (pintype "passive"))
      (node (ref "TP11") (pin "1") (pinfunction "1_1") (pintype "passive"))
    )
    (net (code "145") (name "V-") (class "Default")
      (node (ref "C33") (pin "-") (pinfunction "2_-") (pintype "passive"))
      (node (ref "C36") (pin "-") (pinfunction "2_-") (pintype "passive"))
      (node (ref "FB5") (pin "1") (pinfunction "1_1") (pintype "passive"))
      (node (ref "IC11") (pin "1") (pinfunction "OUT_1") (pintype "output"))
      (node (ref "J2") (pin "1") (pinfunction "1_1") (pintype "passive"))
      (node (ref "J3") (pin "1") (pinfunction "1_1") (pintype "passive"))
      (node (ref "TP21") (pin "1") (pinfunction "1_1") (pintype "passive"))
    )
    (net (code "146") (name "unconnected-(CON5-~{RST}-Pad2)") (class "Default")
      (node (ref "CON5") (pin "2") (pinfunction "~{RST}_2") (pintype "bidirectional"))
    )
    (net (code "147") (name "unconnected-(IC2A-PA02-Pad15)") (class "Default")
      (node (ref "IC2") (pin "15") (pinfunction "PA02_15") (pintype "bidirectional"))
    )
    (net (code "148") (name "unconnected-(IC2A-PA27-Pad26)") (class "Default")
      (node (ref "IC2") (pin "26") (pinfunction "PA27_26") (pintype "bidirectional"))
    )
    (net (code "149") (name "unconnected-(IC2A-PA28-Pad28)") (class "Default")
      (node (ref "IC2") (pin "28") (pinfunction "PA28_28") (pintype "bidirectional"))
    )
    (net (code "150") (name "unconnected-(IC2A-PA29-Pad23)") (class "Default")
      (node (ref "IC2") (pin "23") (pinfunction "PA29_23") (pintype "bidirectional"))
    )
    (net (code "151") (name "unconnected-(IC2A-PA30-Pad14)") (class "Default")
      (node (ref "IC2") (pin "14") (pinfunction "PA30_14") (pintype "bidirectional"))
    )
    (net (code "152") (name "unconnected-(IC2A-PA31-Pad29)") (class "Default")
      (node (ref "IC2") (pin "29") (pinfunction "PA31_29") (pintype "bidirectional"))
    )
    (net (code "153") (name "unconnected-(IC2A-PB00-Pad30)") (class "Default")
      (node (ref "IC2") (pin "30") (pinfunction "PB00_30") (pintype "bidirectional"))
    )
    (net (code "154") (name "unconnected-(IC2A-PB01-Pad27)") (class "Default")
      (node (ref "IC2") (pin "27") (pinfunction "PB01_27") (pintype "bidirectional"))
    )
    (net (code "155") (name "unconnected-(IC2A-PB02-Pad25)") (class "Default")
      (node (ref "IC2") (pin "25") (pinfunction "PB02_25") (pintype "bidirectional"))
    )
    (net (code "156") (name "unconnected-(IC2A-PB03-Pad24)") (class "Default")
      (node (ref "IC2") (pin "24") (pinfunction "PB03_24") (pintype "bidirectional"))
    )
    (net (code "157") (name "unconnected-(IC2A-PB04-Pad22)") (class "Default")
      (node (ref "IC2") (pin "22") (pinfunction "PB04_22") (pintype "bidirectional"))
    )
    (net (code "158") (name "unconnected-(IC2A-PB08-Pad11)") (class "Default")
      (node (ref "IC2") (pin "11") (pinfunction "PB08_11") (pintype "bidirectional"))
    )
    (net (code "159") (name "unconnected-(IC2A-PB09-Pad17)") (class "Default")
      (node (ref "IC2") (pin "17") (pinfunction "PB09_17") (pintype "bidirectional"))
    )
    (net (code "160") (name "unconnected-(IC2A-PB11-Pad31)") (class "Default")
      (node (ref "IC2") (pin "31") (pinfunction "PB11_31") (pintype "bidirectional"))
    )
    (net (code "161") (name "unconnected-(IC2A-PC05-Pad12)") (class "Default")
      (node (ref "IC2") (pin "12") (pinfunction "PC05_12") (pintype "bidirectional"))
    )
    (net (code "162") (name "unconnected-(IC2A-PX12-Pad34)") (class "Default")
      (node (ref "IC2") (pin "34") (pinfunction "PX12_34") (pintype "bidirectional"))
    )
    (net (code "163") (name "unconnected-(IC2A-PX13-Pad33)") (class "Default")
      (node (ref "IC2") (pin "33") (pinfunction "PX13_33") (pintype "bidirectional"))
    )
    (net (code "164") (name "unconnected-(IC2A-PX19-Pad35)") (class "Default")
      (node (ref "IC2") (pin "35") (pinfunction "PX19_35") (pintype "bidirectional"))
    )
    (net (code "165") (name "unconnected-(IC2A-PX40-Pad36)") (class "Default")
      (node (ref "IC2") (pin "36") (pinfunction "PX40_36") (pintype "bidirectional"))
    )
    (net (code "166") (name "unconnected-(IC2B-PX00-Pad55)") (class "Default")
      (node (ref "IC2") (pin "55") (pinfunction "PX00_55") (pintype "bidirectional"))
    )
    (net (code "167") (name "unconnected-(IC2B-PX01-Pad59)") (class "Default")
      (node (ref "IC2") (pin "59") (pinfunction "PX01_59") (pintype "bidirectional"))
    )
    (net (code "168") (name "unconnected-(IC2B-PX02-Pad62)") (class "Default")
      (node (ref "IC2") (pin "62") (pinfunction "PX02_62") (pintype "bidirectional"))
    )
    (net (code "169") (name "unconnected-(IC2B-PX03-Pad63)") (class "Default")
      (node (ref "IC2") (pin "63") (pinfunction "PX03_63") (pintype "bidirectional"))
    )
    (net (code "170") (name "unconnected-(IC2B-PX06-Pad53)") (class "Default")
      (node (ref "IC2") (pin "53") (pinfunction "PX06_53") (pintype "bidirectional"))
    )
    (net (code "171") (name "unconnected-(IC2B-PX07-Pad54)") (class "Default")
      (node (ref "IC2") (pin "54") (pinfunction "PX07_54") (pintype "bidirectional"))
    )
    (net (code "172") (name "unconnected-(IC2B-PX08-Pad50)") (class "Default")
      (node (ref "IC2") (pin "50") (pinfunction "PX08_50") (pintype "bidirectional"))
    )
    (net (code "173") (name "unconnected-(IC2B-PX09-Pad49)") (class "Default")
      (node (ref "IC2") (pin "49") (pinfunction "PX09_49") (pintype "bidirectional"))
    )
    (net (code "174") (name "unconnected-(IC2B-PX10-Pad37)") (class "Default")
      (node (ref "IC2") (pin "37") (pinfunction "PX10_37") (pintype "bidirectional"))
    )
    (net (code "175") (name "unconnected-(IC2B-PX11-Pad67)") (class "Default")
      (node (ref "IC2") (pin "67") (pinfunction "PX11_67") (pintype "bidirectional"))
    )
    (net (code "176") (name "unconnected-(IC2B-PX14-Pad68)") (class "Default")
      (node (ref "IC2") (pin "68") (pinfunction "PX14_68") (pintype "bidirectional"))
    )
    (net (code "177") (name "unconnected-(IC2B-PX15-Pad40)") (class "Default")
      (node (ref "IC2") (pin "40") (pinfunction "PX15_40") (pintype "bidirectional"))
    )
    (net (code "178") (name "unconnected-(IC2B-PX22-Pad72)") (class "Default")
      (node (ref "IC2") (pin "72") (pinfunction "PX22_72") (pintype "bidirectional"))
    )
    (net (code "179") (name "unconnected-(IC2B-PX34-Pad61)") (class "Default")
      (node (ref "IC2") (pin "61") (pinfunction "PX34_61") (pintype "bidirectional"))
    )
    (net (code "180") (name "unconnected-(IC2B-PX36-Pad44)") (class "Default")
      (node (ref "IC2") (pin "44") (pinfunction "PX36_44") (pintype "bidirectional"))
    )
    (net (code "181") (name "unconnected-(IC2B-PX37-Pad45)") (class "Default")
      (node (ref "IC2") (pin "45") (pinfunction "PX37_45") (pintype "bidirectional"))
    )
    (net (code "182") (name "unconnected-(IC2B-PX38-Pad51)") (class "Default")
      (node (ref "IC2") (pin "51") (pinfunction "PX38_51") (pintype "bidirectional"))
    )
    (net (code "183") (name "unconnected-(IC2B-PX39-Pad52)") (class "Default")
      (node (ref "IC2") (pin "52") (pinfunction "PX39_52") (pintype "bidirectional"))
    )
    (net (code "184") (name "unconnected-(IC2B-PX41-Pad71)") (class "Default")
      (node (ref "IC2") (pin "71") (pinfunction "PX41_71") (pintype "bidirectional"))
    )
    (net (code "185") (name "unconnected-(IC2B-PX42-Pad69)") (class "Default")
      (node (ref "IC2") (pin "69") (pinfunction "PX42_69") (pintype "bidirectional"))
    )
    (net (code "186") (name "unconnected-(IC2B-PX44-Pad66)") (class "Default")
      (node (ref "IC2") (pin "66") (pinfunction "PX44_66") (pintype "bidirectional"))
    )
    (net (code "187") (name "unconnected-(IC2B-PX45-Pad70)") (class "Default")
      (node (ref "IC2") (pin "70") (pinfunction "PX45_70") (pintype "bidirectional"))
    )
    (net (code "188") (name "unconnected-(IC2B-PX47-Pad39)") (class "Default")
      (node (ref "IC2") (pin "39") (pinfunction "PX47_39") (pintype "bidirectional"))
    )
    (net (code "189") (name "unconnected-(IC2B-PX48-Pad41)") (class "Default")
      (node (ref "IC2") (pin "41") (pinfunction "PX48_41") (pintype "bidirectional"))
    )
    (net (code "190") (name "unconnected-(IC2B-PX49-Pad43)") (class "Default")
      (node (ref "IC2") (pin "43") (pinfunction "PX49_43") (pintype "bidirectional"))
    )
    (net (code "191") (name "unconnected-(IC2B-PX53-Pad42)") (class "Default")
      (node (ref "IC2") (pin "42") (pinfunction "PX53_42") (pintype "bidirectional"))
    )
    (net (code "192") (name "unconnected-(IC2B-PX54-Pad46)") (class "Default")
      (node (ref "IC2") (pin "46") (pinfunction "PX54_46") (pintype "bidirectional"))
    )
    (net (code "193") (name "unconnected-(IC2B-PX58-Pad57)") (class "Default")
      (node (ref "IC2") (pin "57") (pinfunction "PX58_57") (pintype "bidirectional"))
    )
    (net (code "194") (name "unconnected-(IC2B-PX59-Pad56)") (class "Default")
      (node (ref "IC2") (pin "56") (pinfunction "PX59_56") (pintype "bidirectional"))
    )
    (net (code "195") (name "unconnected-(IC2C-PA14-Pad100)") (class "Default")
      (node (ref "IC2") (pin "100") (pinfunction "PA14_100") (pintype "bidirectional"))
    )
    (net (code "196") (name "unconnected-(IC2C-PA15-Pad101)") (class "Default")
      (node (ref "IC2") (pin "101") (pinfunction "PA15_101") (pintype "bidirectional"))
    )
    (net (code "197") (name "unconnected-(IC2C-PC00-Pad98)") (class "Default")
      (node (ref "IC2") (pin "98") (pinfunction "PC00_98") (pintype "bidirectional"))
    )
    (net (code "198") (name "unconnected-(IC2C-PC01-Pad99)") (class "Default")
      (node (ref "IC2") (pin "99") (pinfunction "PC01_99") (pintype "bidirectional"))
    )
    (net (code "199") (name "unconnected-(IC2C-PX17-Pad83)") (class "Default")
      (node (ref "IC2") (pin "83") (pinfunction "PX17_83") (pintype "bidirectional"))
    )
    (net (code "200") (name "unconnected-(IC2C-PX18-Pad84)") (class "Default")
      (node (ref "IC2") (pin "84") (pinfunction "PX18_84") (pintype "bidirectional"))
    )
    (net (code "201") (name "unconnected-(IC2C-PX20-Pad73)") (class "Default")
      (node (ref "IC2") (pin "73") (pinfunction "PX20_73") (pintype "bidirectional"))
    )
    (net (code "202") (name "unconnected-(IC2C-PX21-Pad80)") (class "Default")
      (node (ref "IC2") (pin "80") (pinfunction "PX21_80") (pintype "bidirectional"))
    )
    (net (code "203") (name "unconnected-(IC2C-PX25-Pad92)") (class "Default")
      (node (ref "IC2") (pin "92") (pinfunction "PX25_92") (pintype "bidirectional"))
    )
    (net (code "204") (name "unconnected-(IC2C-PX26-Pad90)") (class "Default")
      (node (ref "IC2") (pin "90") (pinfunction "PX26_90") (pintype "bidirectional"))
    )
    (net (code "205") (name "unconnected-(IC2C-PX28-Pad91)") (class "Default")
      (node (ref "IC2") (pin "91") (pinfunction "PX28_91") (pintype "bidirectional"))
    )
    (net (code "206") (name "unconnected-(IC2C-PX30-Pad96)") (class "Default")
      (node (ref "IC2") (pin "96") (pinfunction "PX30_96") (pintype "bidirectional"))
    )
    (net (code "207") (name "unconnected-(IC2C-PX31-Pad97)") (class "Default")
      (node (ref "IC2") (pin "97") (pinfunction "PX31_97") (pintype "bidirectional"))
    )
    (net (code "208") (name "unconnected-(IC2C-PX32-Pad93)") (class "Default")
      (node (ref "IC2") (pin "93") (pinfunction "PX32_93") (pintype "bidirectional"))
    )
    (net (code "209") (name "unconnected-(IC2C-PX43-Pad88)") (class "Default")
      (node (ref "IC2") (pin "88") (pinfunction "PX43_88") (pintype "bidirectional"))
    )
    (net (code "210") (name "unconnected-(IC2C-PX46-Pad74)") (class "Default")
      (node (ref "IC2") (pin "74") (pinfunction "PX46_74") (pintype "bidirectional"))
    )
    (net (code "211") (name "unconnected-(IC2C-PX50-Pad75)") (class "Default")
      (node (ref "IC2") (pin "75") (pinfunction "PX50_75") (pintype "bidirectional"))
    )
    (net (code "212") (name "unconnected-(IC2C-PX51-Pad77)") (class "Default")
      (node (ref "IC2") (pin "77") (pinfunction "PX51_77") (pintype "bidirectional"))
    )
    (net (code "213") (name "unconnected-(IC2C-PX52-Pad87)") (class "Default")
      (node (ref "IC2") (pin "87") (pinfunction "PX52_87") (pintype "bidirectional"))
    )
    (net (code "214") (name "unconnected-(IC2C-PX55-Pad79)") (class "Default")
      (node (ref "IC2") (pin "79") (pinfunction "PX55_79") (pintype "bidirectional"))
    )
    (net (code "215") (name "unconnected-(IC2C-PX56-Pad78)") (class "Default")
      (node (ref "IC2") (pin "78") (pinfunction "PX56_78") (pintype "bidirectional"))
    )
    (net (code "216") (name "unconnected-(IC2C-PX57-Pad76)") (class "Default")
      (node (ref "IC2") (pin "76") (pinfunction "PX57_76") (pintype "bidirectional"))
    )
    (net (code "217") (name "unconnected-(IC2C-TCK-Pad107)") (class "Default")
      (node (ref "IC2") (pin "107") (pinfunction "TCK_107") (pintype "bidirectional"))
    )
    (net (code "218") (name "unconnected-(IC2C-TDI-Pad108)") (class "Default")
      (node (ref "IC2") (pin "108") (pinfunction "TDI_108") (pintype "bidirectional"))
    )
    (net (code "219") (name "unconnected-(IC2C-TDO-Pad105)") (class "Default")
      (node (ref "IC2") (pin "105") (pinfunction "TDO_105") (pintype "bidirectional"))
    )
    (net (code "220") (name "unconnected-(IC2C-TMS-Pad104)") (class "Default")
      (node (ref "IC2") (pin "104") (pinfunction "TMS_104") (pintype "bidirectional"))
    )
    (net (code "221") (name "unconnected-(IC2D-PA00-Pad122)") (class "Default")
      (node (ref "IC2") (pin "122") (pinfunction "PA00_122") (pintype "bidirectional"))
    )
    (net (code "222") (name "unconnected-(IC2D-PA01-Pad123)") (class "Default")
      (node (ref "IC2") (pin "123") (pinfunction "PA01_123") (pintype "bidirectional"))
    )
    (net (code "223") (name "unconnected-(IC2D-PA03-Pad125)") (class "Default")
      (node (ref "IC2") (pin "125") (pinfunction "PA03_125") (pintype "bidirectional"))
    )
    (net (code "224") (name "unconnected-(IC2D-PA04-Pad126)") (class "Default")
      (node (ref "IC2") (pin "126") (pinfunction "PA04_126") (pintype "bidirectional"))
    )
    (net (code "225") (name "unconnected-(IC2D-PA05-Pad124)") (class "Default")
      (node (ref "IC2") (pin "124") (pinfunction "PA05_124") (pintype "bidirectional"))
    )
    (net (code "226") (name "unconnected-(IC2D-PA06-Pad127)") (class "Default")
      (node (ref "IC2") (pin "127") (pinfunction "PA06_127") (pintype "bidirectional"))
    )
    (net (code "227") (name "unconnected-(IC2D-PA07-Pad133)") (class "Default")
      (node (ref "IC2") (pin "133") (pinfunction "PA07_133") (pintype "bidirectional"))
    )
    (net (code "228") (name "unconnected-(IC2D-PA08-Pad137)") (class "Default")
      (node (ref "IC2") (pin "137") (pinfunction "PA08_137") (pintype "bidirectional"))
    )
    (net (code "229") (name "unconnected-(IC2D-PA09-Pad139)") (class "Default")
      (node (ref "IC2") (pin "139") (pinfunction "PA09_139") (pintype "bidirectional"))
    )
    (net (code "230") (name "unconnected-(IC2D-PA10-Pad138)") (class "Default")
      (node (ref "IC2") (pin "138") (pinfunction "PA10_138") (pintype "bidirectional"))
    )
    (net (code "231") (name "unconnected-(IC2D-PA11-Pad136)") (class "Default")
      (node (ref "IC2") (pin "136") (pinfunction "PA11_136") (pintype "bidirectional"))
    )
    (net (code "232") (name "unconnected-(IC2D-PA12-Pad132)") (class "Default")
      (node (ref "IC2") (pin "132") (pinfunction "PA12_132") (pintype "bidirectional"))
    )
    (net (code "233") (name "unconnected-(IC2D-PA13-Pad129)") (class "Default")
      (node (ref "IC2") (pin "129") (pinfunction "PA13_129") (pintype "bidirectional"))
    )
    (net (code "234") (name "unconnected-(IC2D-PA16-Pad128)") (class "Default")
      (node (ref "IC2") (pin "128") (pinfunction "PA16_128") (pintype "bidirectional"))
    )
    (net (code "235") (name "unconnected-(IC2D-PA17-Pad116)") (class "Default")
      (node (ref "IC2") (pin "116") (pinfunction "PA17_116") (pintype "bidirectional"))
    )
    (net (code "236") (name "unconnected-(IC2D-PA18-Pad115)") (class "Default")
      (node (ref "IC2") (pin "115") (pinfunction "PA18_115") (pintype "bidirectional"))
    )
    (net (code "237") (name "unconnected-(IC2D-PA19-Pad114)") (class "Default")
      (node (ref "IC2") (pin "114") (pinfunction "PA19_114") (pintype "bidirectional"))
    )
    (net (code "238") (name "unconnected-(IC2D-PA20-Pad113)") (class "Default")
      (node (ref "IC2") (pin "113") (pinfunction "PA20_113") (pintype "bidirectional"))
    )
    (net (code "239") (name "unconnected-(IC2D-PA21-Pad109)") (class "Default")
      (node (ref "IC2") (pin "109") (pinfunction "PA21_109") (pintype "bidirectional"))
    )
    (net (code "240") (name "unconnected-(IC2D-PA23-Pad111)") (class "Default")
      (node (ref "IC2") (pin "111") (pinfunction "PA23_111") (pintype "bidirectional"))
    )
    (net (code "241") (name "unconnected-(IC2D-PA24-Pad112)") (class "Default")
      (node (ref "IC2") (pin "112") (pinfunction "PA24_112") (pintype "bidirectional"))
    )
    (net (code "242") (name "unconnected-(IC2D-PA25-Pad119)") (class "Default")
      (node (ref "IC2") (pin "119") (pinfunction "PA25_119") (pintype "bidirectional"))
    )
    (net (code "243") (name "unconnected-(IC2D-PA26-Pad120)") (class "Default")
      (node (ref "IC2") (pin "120") (pinfunction "PA26_120") (pintype "bidirectional"))
    )
    (net (code "244") (name "unconnected-(IC2D-PB05-Pad121)") (class "Default")
      (node (ref "IC2") (pin "121") (pinfunction "PB05_121") (pintype "bidirectional"))
    )
    (net (code "245") (name "unconnected-(IC2D-PB06-Pad134)") (class "Default")
      (node (ref "IC2") (pin "134") (pinfunction "PB06_134") (pintype "bidirectional"))
    )
    (net (code "246") (name "unconnected-(IC2D-PB07-Pad135)") (class "Default")
      (node (ref "IC2") (pin "135") (pinfunction "PB07_135") (pintype "bidirectional"))
    )
    (net (code "247") (name "unconnected-(IC2D-PS22-Pad110)") (class "Default")
      (node (ref "IC2") (pin "110") (pinfunction "PS22_110") (pintype "bidirectional"))
    )
    (net (code "248") (name "unconnected-(IC3-OUT2-Pad6)") (class "Default")
      (node (ref "IC3") (pin "6") (pinfunction "OUT2_6") (pintype "output"))
    )
    (net (code "249") (name "unconnected-(IC6-OUT1-Pad7)") (class "Default")
      (node (ref "IC6") (pin "7") (pinfunction "OUT1_7") (pintype "output"))
    )
    (net (code "250") (name "unconnected-(IC8-DIF0{slash}DZFL-Pad10)") (class "Default")
      (node (ref "IC8") (pin "10") (pinfunction "DIF0/DZFL_10") (pintype "bidirectional"))
    )
    (net (code "251") (name "unconnected-(IC8-DIF1{slash}DZFR-Pad11)") (class "Default")
      (node (ref "IC8") (pin "11") (pinfunction "DIF1/DZFR_11") (pintype "bidirectional"))
    )
    (net (code "252") (name "unconnected-(IC8-NC1-Pad24)") (class "Default")
      (node (ref "IC8") (pin "24") (pinfunction "NC1_24") (pintype "no_connect"))
    )
    (net (code "253") (name "unconnected-(IC8-NC2-Pad37)") (class "Default")
      (node (ref "IC8") (pin "37") (pinfunction "NC2_37") (pintype "no_connect"))
    )
    (net (code "254") (name "unconnected-(IC8-NC3-Pad43)") (class "Default")
      (node (ref "IC8") (pin "43") (pinfunction "NC3_43") (pintype "no_connect"))
    )
    (net (code "255") (name "unconnected-(IC16-IO6{slash}NRST-Pad6)") (class "Default")
      (node (ref "IC16") (pin "6") (pinfunction "IO6/NRST_6") (pintype "bidirectional"))
    )
    (net (code "256") (name "unconnected-(IC16-IO8-Pad8)") (class "Default")
      (node (ref "IC16") (pin "8") (pinfunction "IO8_8") (pintype "bidirectional"))
    )
    (net (code "257") (name "unconnected-(IC16-IO10-Pad10)") (class "Default")
      (node (ref "IC16") (pin "10") (pinfunction "IO10_10") (pintype "bidirectional"))
    )
    (net (code "258") (name "unconnected-(IC16-IO17-Pad17)") (class "Default")
      (node (ref "IC16") (pin "17") (pinfunction "IO17_17") (pintype "bidirectional"))
    )
    (net (code "259") (name "unconnected-(IC20B-OUT-Pad2)") (class "Default")
      (node (ref "IC20") (pin "2") (pinfunction "OUT_2") (pintype "output"))
    )
    (net (code "260") (name "unconnected-(SW1-B1-Pad2)") (class "Default")
      (node (ref "SW1") (pin "2") (pinfunction "B1_2") (pintype "passive"))
    )
    (net (code "261") (name "unconnected-(SW1-B2-Pad9)") (class "Default")
      (node (ref "SW1") (pin "9") (pinfunction "B2_9") (pintype "passive"))
    )
    (net (code "262") (name "unconnected-(SW2-B1-Pad2)") (class "Default")
      (node (ref "SW2") (pin "2") (pinfunction "B1_2") (pintype "passive"))
    )
    (net (code "263") (name "unconnected-(SW2-B2-Pad9)") (class "Default")
      (node (ref "SW2") (pin "9") (pinfunction "B2_9") (pintype "passive"))
    )
  )
)
